# ChromDot_Ring_five_inch.net
KiCad netlist of a schematic drawn in EAGLE
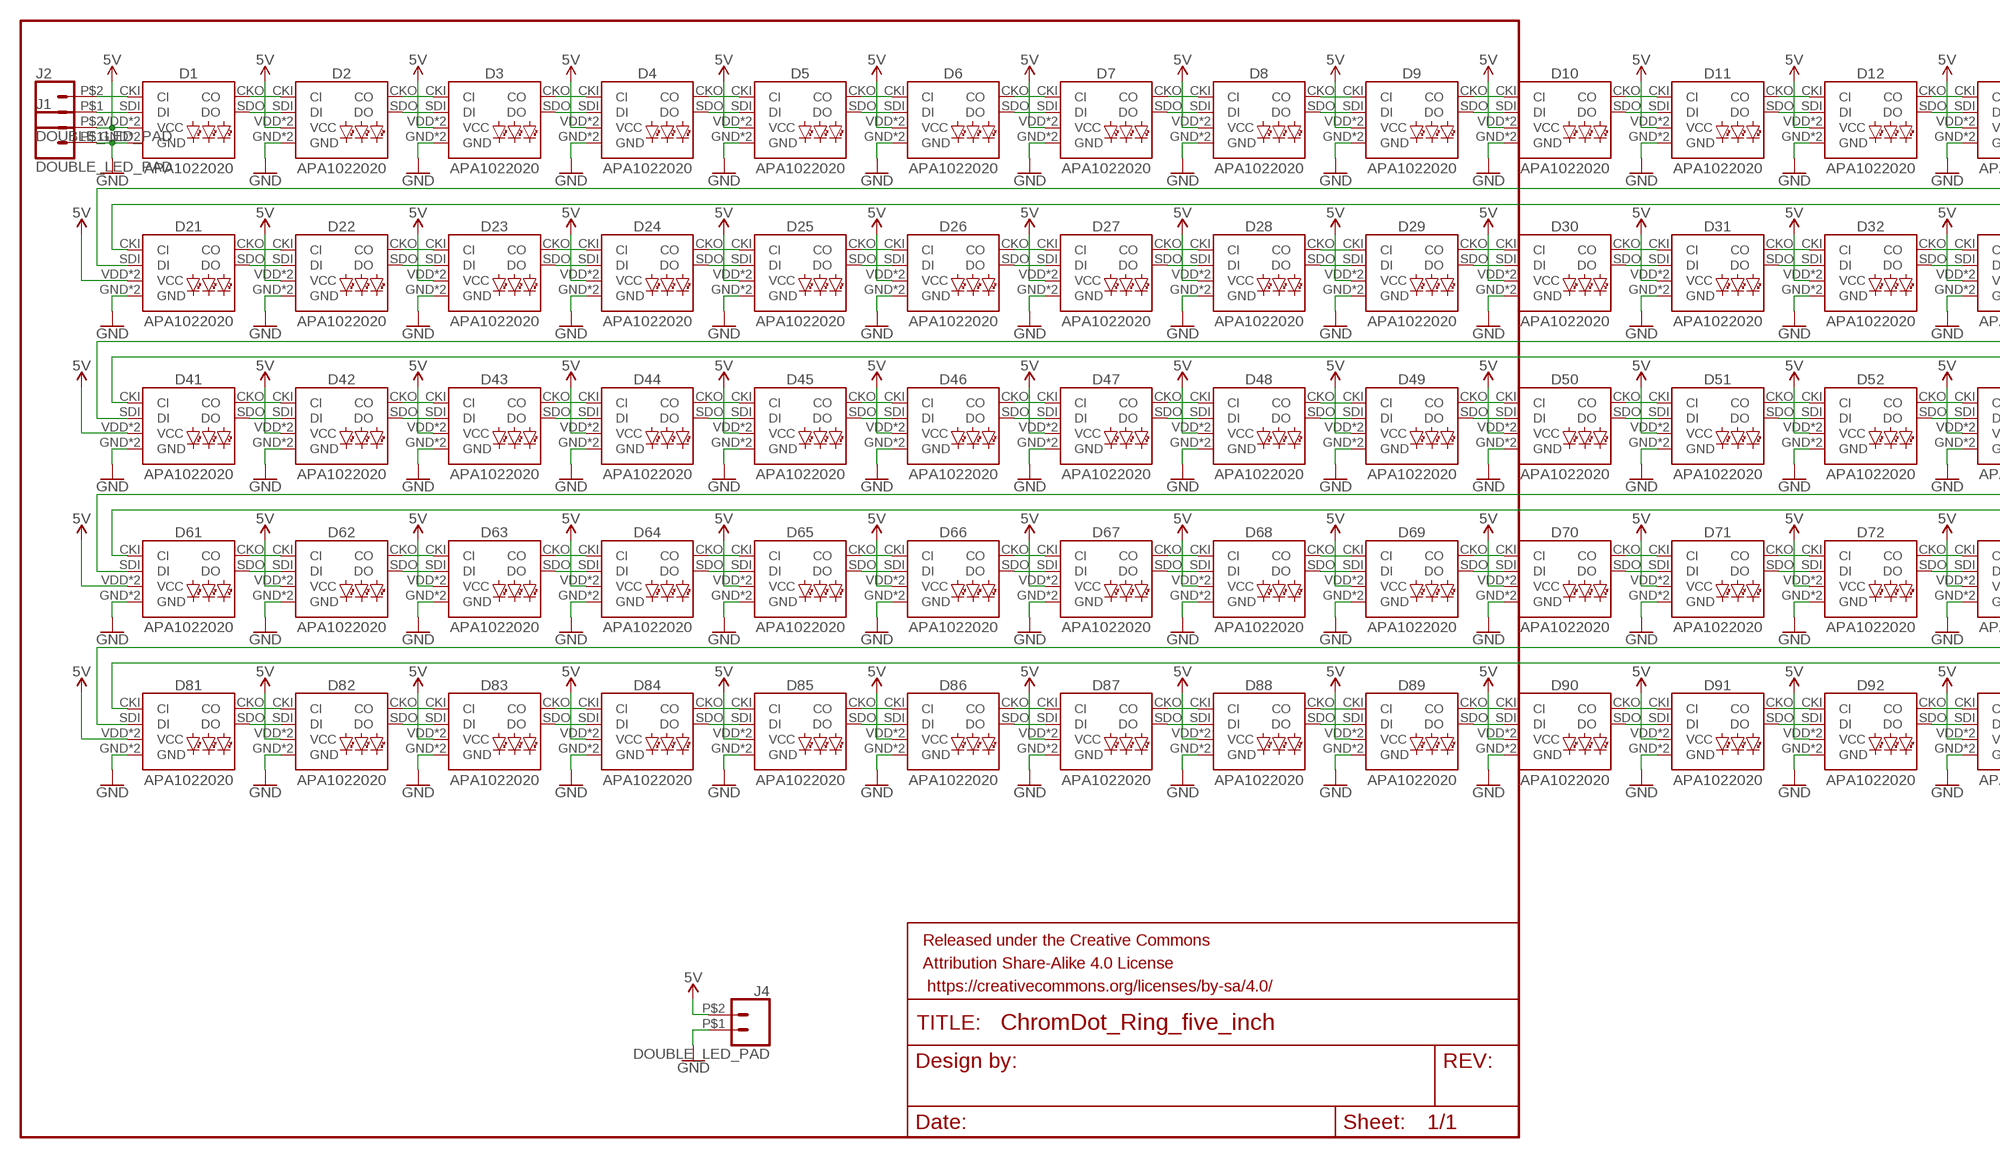
[diagram p0: schematic, sheet 1, part 1 of 2]
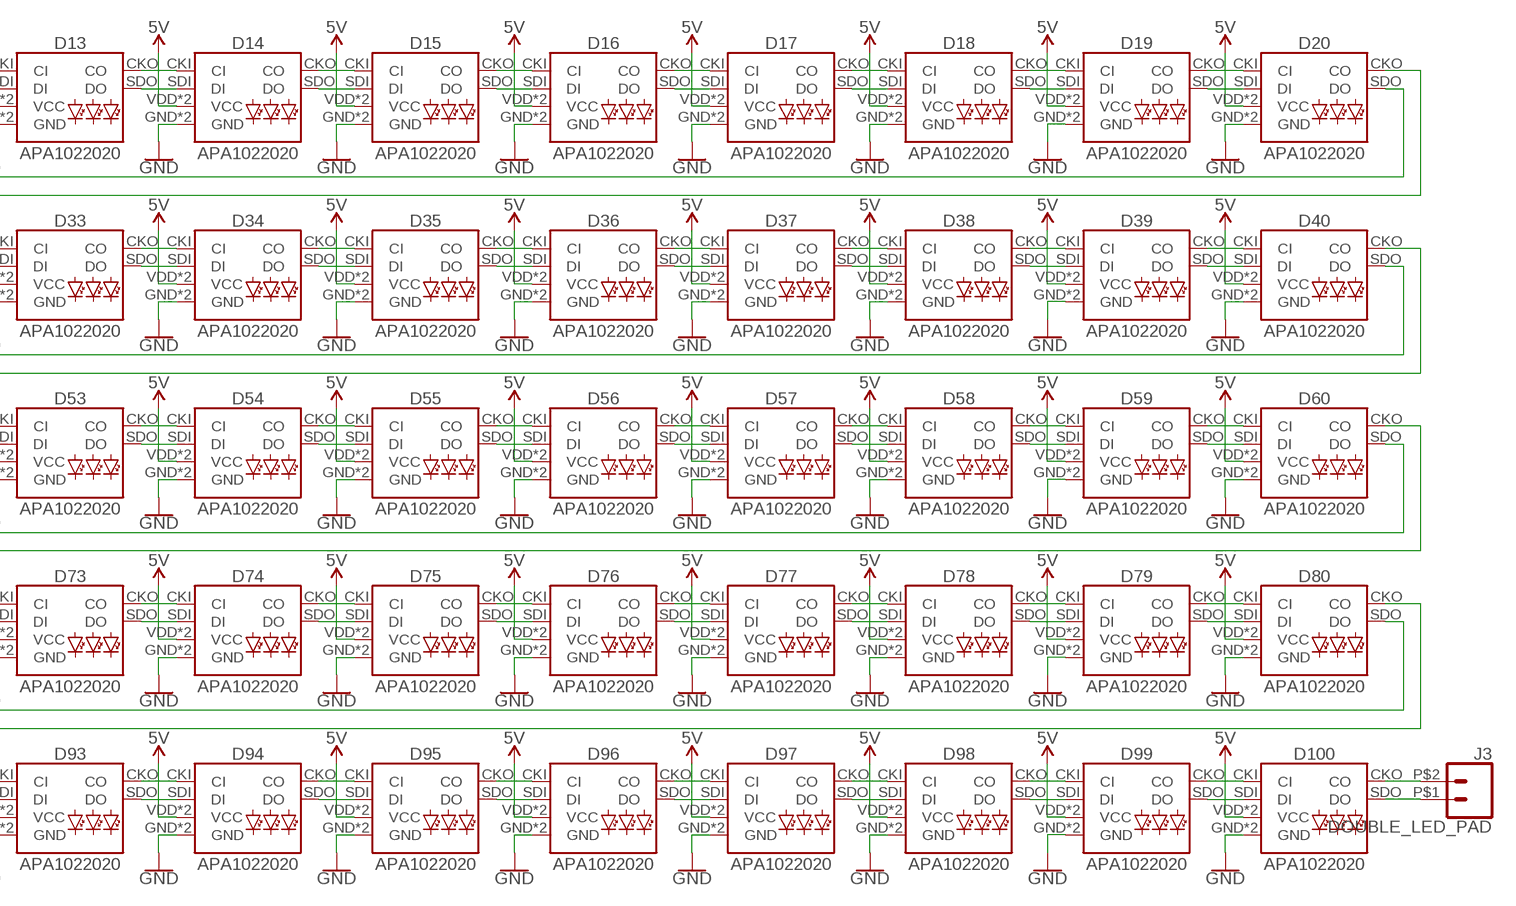
[diagram p1: schematic, sheet 1, part 2 of 2]

(export (version "E")
  (design (tool "Eeschema 10.0.6"))
  (components
    (comp (ref "D1")
      (value "APA1022020")
      (footprint "eagle-import:APA102-2020")
      (libsource (lib "eagle-import") (part "APA1022020"))
    )
    (comp (ref "D2")
      (value "APA1022020")
      (footprint "eagle-import:APA102-2020")
      (libsource (lib "eagle-import") (part "APA1022020"))
    )
    (comp (ref "D3")
      (value "APA1022020")
      (footprint "eagle-import:APA102-2020")
      (libsource (lib "eagle-import") (part "APA1022020"))
    )
    (comp (ref "D4")
      (value "APA1022020")
      (footprint "eagle-import:APA102-2020")
      (libsource (lib "eagle-import") (part "APA1022020"))
    )
    (comp (ref "D5")
      (value "APA1022020")
      (footprint "eagle-import:APA102-2020")
      (libsource (lib "eagle-import") (part "APA1022020"))
    )
    (comp (ref "D6")
      (value "APA1022020")
      (footprint "eagle-import:APA102-2020")
      (libsource (lib "eagle-import") (part "APA1022020"))
    )
    (comp (ref "D7")
      (value "APA1022020")
      (footprint "eagle-import:APA102-2020")
      (libsource (lib "eagle-import") (part "APA1022020"))
    )
    (comp (ref "D8")
      (value "APA1022020")
      (footprint "eagle-import:APA102-2020")
      (libsource (lib "eagle-import") (part "APA1022020"))
    )
    (comp (ref "D9")
      (value "APA1022020")
      (footprint "eagle-import:APA102-2020")
      (libsource (lib "eagle-import") (part "APA1022020"))
    )
    (comp (ref "D10")
      (value "APA1022020")
      (footprint "eagle-import:APA102-2020")
      (libsource (lib "eagle-import") (part "APA1022020"))
    )
    (comp (ref "D11")
      (value "APA1022020")
      (footprint "eagle-import:APA102-2020")
      (libsource (lib "eagle-import") (part "APA1022020"))
    )
    (comp (ref "D12")
      (value "APA1022020")
      (footprint "eagle-import:APA102-2020")
      (libsource (lib "eagle-import") (part "APA1022020"))
    )
    (comp (ref "D13")
      (value "APA1022020")
      (footprint "eagle-import:APA102-2020")
      (libsource (lib "eagle-import") (part "APA1022020"))
    )
    (comp (ref "D14")
      (value "APA1022020")
      (footprint "eagle-import:APA102-2020")
      (libsource (lib "eagle-import") (part "APA1022020"))
    )
    (comp (ref "D15")
      (value "APA1022020")
      (footprint "eagle-import:APA102-2020")
      (libsource (lib "eagle-import") (part "APA1022020"))
    )
    (comp (ref "D16")
      (value "APA1022020")
      (footprint "eagle-import:APA102-2020")
      (libsource (lib "eagle-import") (part "APA1022020"))
    )
    (comp (ref "D17")
      (value "APA1022020")
      (footprint "eagle-import:APA102-2020")
      (libsource (lib "eagle-import") (part "APA1022020"))
    )
    (comp (ref "D18")
      (value "APA1022020")
      (footprint "eagle-import:APA102-2020")
      (libsource (lib "eagle-import") (part "APA1022020"))
    )
    (comp (ref "D19")
      (value "APA1022020")
      (footprint "eagle-import:APA102-2020")
      (libsource (lib "eagle-import") (part "APA1022020"))
    )
    (comp (ref "D20")
      (value "APA1022020")
      (footprint "eagle-import:APA102-2020")
      (libsource (lib "eagle-import") (part "APA1022020"))
    )
    (comp (ref "D21")
      (value "APA1022020")
      (footprint "eagle-import:APA102-2020")
      (libsource (lib "eagle-import") (part "APA1022020"))
    )
    (comp (ref "D22")
      (value "APA1022020")
      (footprint "eagle-import:APA102-2020")
      (libsource (lib "eagle-import") (part "APA1022020"))
    )
    (comp (ref "D23")
      (value "APA1022020")
      (footprint "eagle-import:APA102-2020")
      (libsource (lib "eagle-import") (part "APA1022020"))
    )
    (comp (ref "D24")
      (value "APA1022020")
      (footprint "eagle-import:APA102-2020")
      (libsource (lib "eagle-import") (part "APA1022020"))
    )
    (comp (ref "D25")
      (value "APA1022020")
      (footprint "eagle-import:APA102-2020")
      (libsource (lib "eagle-import") (part "APA1022020"))
    )
    (comp (ref "D26")
      (value "APA1022020")
      (footprint "eagle-import:APA102-2020")
      (libsource (lib "eagle-import") (part "APA1022020"))
    )
    (comp (ref "D27")
      (value "APA1022020")
      (footprint "eagle-import:APA102-2020")
      (libsource (lib "eagle-import") (part "APA1022020"))
    )
    (comp (ref "D28")
      (value "APA1022020")
      (footprint "eagle-import:APA102-2020")
      (libsource (lib "eagle-import") (part "APA1022020"))
    )
    (comp (ref "D29")
      (value "APA1022020")
      (footprint "eagle-import:APA102-2020")
      (libsource (lib "eagle-import") (part "APA1022020"))
    )
    (comp (ref "D30")
      (value "APA1022020")
      (footprint "eagle-import:APA102-2020")
      (libsource (lib "eagle-import") (part "APA1022020"))
    )
    (comp (ref "D31")
      (value "APA1022020")
      (footprint "eagle-import:APA102-2020")
      (libsource (lib "eagle-import") (part "APA1022020"))
    )
    (comp (ref "D32")
      (value "APA1022020")
      (footprint "eagle-import:APA102-2020")
      (libsource (lib "eagle-import") (part "APA1022020"))
    )
    (comp (ref "D33")
      (value "APA1022020")
      (footprint "eagle-import:APA102-2020")
      (libsource (lib "eagle-import") (part "APA1022020"))
    )
    (comp (ref "D34")
      (value "APA1022020")
      (footprint "eagle-import:APA102-2020")
      (libsource (lib "eagle-import") (part "APA1022020"))
    )
    (comp (ref "D35")
      (value "APA1022020")
      (footprint "eagle-import:APA102-2020")
      (libsource (lib "eagle-import") (part "APA1022020"))
    )
    (comp (ref "D36")
      (value "APA1022020")
      (footprint "eagle-import:APA102-2020")
      (libsource (lib "eagle-import") (part "APA1022020"))
    )
    (comp (ref "D37")
      (value "APA1022020")
      (footprint "eagle-import:APA102-2020")
      (libsource (lib "eagle-import") (part "APA1022020"))
    )
    (comp (ref "D38")
      (value "APA1022020")
      (footprint "eagle-import:APA102-2020")
      (libsource (lib "eagle-import") (part "APA1022020"))
    )
    (comp (ref "D39")
      (value "APA1022020")
      (footprint "eagle-import:APA102-2020")
      (libsource (lib "eagle-import") (part "APA1022020"))
    )
    (comp (ref "D40")
      (value "APA1022020")
      (footprint "eagle-import:APA102-2020")
      (libsource (lib "eagle-import") (part "APA1022020"))
    )
    (comp (ref "D41")
      (value "APA1022020")
      (footprint "eagle-import:APA102-2020")
      (libsource (lib "eagle-import") (part "APA1022020"))
    )
    (comp (ref "D42")
      (value "APA1022020")
      (footprint "eagle-import:APA102-2020")
      (libsource (lib "eagle-import") (part "APA1022020"))
    )
    (comp (ref "D43")
      (value "APA1022020")
      (footprint "eagle-import:APA102-2020")
      (libsource (lib "eagle-import") (part "APA1022020"))
    )
    (comp (ref "D44")
      (value "APA1022020")
      (footprint "eagle-import:APA102-2020")
      (libsource (lib "eagle-import") (part "APA1022020"))
    )
    (comp (ref "D45")
      (value "APA1022020")
      (footprint "eagle-import:APA102-2020")
      (libsource (lib "eagle-import") (part "APA1022020"))
    )
    (comp (ref "D46")
      (value "APA1022020")
      (footprint "eagle-import:APA102-2020")
      (libsource (lib "eagle-import") (part "APA1022020"))
    )
    (comp (ref "D47")
      (value "APA1022020")
      (footprint "eagle-import:APA102-2020")
      (libsource (lib "eagle-import") (part "APA1022020"))
    )
    (comp (ref "D48")
      (value "APA1022020")
      (footprint "eagle-import:APA102-2020")
      (libsource (lib "eagle-import") (part "APA1022020"))
    )
    (comp (ref "D49")
      (value "APA1022020")
      (footprint "eagle-import:APA102-2020")
      (libsource (lib "eagle-import") (part "APA1022020"))
    )
    (comp (ref "D50")
      (value "APA1022020")
      (footprint "eagle-import:APA102-2020")
      (libsource (lib "eagle-import") (part "APA1022020"))
    )
    (comp (ref "D51")
      (value "APA1022020")
      (footprint "eagle-import:APA102-2020")
      (libsource (lib "eagle-import") (part "APA1022020"))
    )
    (comp (ref "D52")
      (value "APA1022020")
      (footprint "eagle-import:APA102-2020")
      (libsource (lib "eagle-import") (part "APA1022020"))
    )
    (comp (ref "D53")
      (value "APA1022020")
      (footprint "eagle-import:APA102-2020")
      (libsource (lib "eagle-import") (part "APA1022020"))
    )
    (comp (ref "D54")
      (value "APA1022020")
      (footprint "eagle-import:APA102-2020")
      (libsource (lib "eagle-import") (part "APA1022020"))
    )
    (comp (ref "D55")
      (value "APA1022020")
      (footprint "eagle-import:APA102-2020")
      (libsource (lib "eagle-import") (part "APA1022020"))
    )
    (comp (ref "D56")
      (value "APA1022020")
      (footprint "eagle-import:APA102-2020")
      (libsource (lib "eagle-import") (part "APA1022020"))
    )
    (comp (ref "D57")
      (value "APA1022020")
      (footprint "eagle-import:APA102-2020")
      (libsource (lib "eagle-import") (part "APA1022020"))
    )
    (comp (ref "D58")
      (value "APA1022020")
      (footprint "eagle-import:APA102-2020")
      (libsource (lib "eagle-import") (part "APA1022020"))
    )
    (comp (ref "D59")
      (value "APA1022020")
      (footprint "eagle-import:APA102-2020")
      (libsource (lib "eagle-import") (part "APA1022020"))
    )
    (comp (ref "D60")
      (value "APA1022020")
      (footprint "eagle-import:APA102-2020")
      (libsource (lib "eagle-import") (part "APA1022020"))
    )
    (comp (ref "D61")
      (value "APA1022020")
      (footprint "eagle-import:APA102-2020")
      (libsource (lib "eagle-import") (part "APA1022020"))
    )
    (comp (ref "D62")
      (value "APA1022020")
      (footprint "eagle-import:APA102-2020")
      (libsource (lib "eagle-import") (part "APA1022020"))
    )
    (comp (ref "D63")
      (value "APA1022020")
      (footprint "eagle-import:APA102-2020")
      (libsource (lib "eagle-import") (part "APA1022020"))
    )
    (comp (ref "D64")
      (value "APA1022020")
      (footprint "eagle-import:APA102-2020")
      (libsource (lib "eagle-import") (part "APA1022020"))
    )
    (comp (ref "D65")
      (value "APA1022020")
      (footprint "eagle-import:APA102-2020")
      (libsource (lib "eagle-import") (part "APA1022020"))
    )
    (comp (ref "D66")
      (value "APA1022020")
      (footprint "eagle-import:APA102-2020")
      (libsource (lib "eagle-import") (part "APA1022020"))
    )
    (comp (ref "D67")
      (value "APA1022020")
      (footprint "eagle-import:APA102-2020")
      (libsource (lib "eagle-import") (part "APA1022020"))
    )
    (comp (ref "D68")
      (value "APA1022020")
      (footprint "eagle-import:APA102-2020")
      (libsource (lib "eagle-import") (part "APA1022020"))
    )
    (comp (ref "D69")
      (value "APA1022020")
      (footprint "eagle-import:APA102-2020")
      (libsource (lib "eagle-import") (part "APA1022020"))
    )
    (comp (ref "D70")
      (value "APA1022020")
      (footprint "eagle-import:APA102-2020")
      (libsource (lib "eagle-import") (part "APA1022020"))
    )
    (comp (ref "D71")
      (value "APA1022020")
      (footprint "eagle-import:APA102-2020")
      (libsource (lib "eagle-import") (part "APA1022020"))
    )
    (comp (ref "D72")
      (value "APA1022020")
      (footprint "eagle-import:APA102-2020")
      (libsource (lib "eagle-import") (part "APA1022020"))
    )
    (comp (ref "D73")
      (value "APA1022020")
      (footprint "eagle-import:APA102-2020")
      (libsource (lib "eagle-import") (part "APA1022020"))
    )
    (comp (ref "D74")
      (value "APA1022020")
      (footprint "eagle-import:APA102-2020")
      (libsource (lib "eagle-import") (part "APA1022020"))
    )
    (comp (ref "D75")
      (value "APA1022020")
      (footprint "eagle-import:APA102-2020")
      (libsource (lib "eagle-import") (part "APA1022020"))
    )
    (comp (ref "D76")
      (value "APA1022020")
      (footprint "eagle-import:APA102-2020")
      (libsource (lib "eagle-import") (part "APA1022020"))
    )
    (comp (ref "D77")
      (value "APA1022020")
      (footprint "eagle-import:APA102-2020")
      (libsource (lib "eagle-import") (part "APA1022020"))
    )
    (comp (ref "D78")
      (value "APA1022020")
      (footprint "eagle-import:APA102-2020")
      (libsource (lib "eagle-import") (part "APA1022020"))
    )
    (comp (ref "D79")
      (value "APA1022020")
      (footprint "eagle-import:APA102-2020")
      (libsource (lib "eagle-import") (part "APA1022020"))
    )
    (comp (ref "D80")
      (value "APA1022020")
      (footprint "eagle-import:APA102-2020")
      (libsource (lib "eagle-import") (part "APA1022020"))
    )
    (comp (ref "D81")
      (value "APA1022020")
      (footprint "eagle-import:APA102-2020")
      (libsource (lib "eagle-import") (part "APA1022020"))
    )
    (comp (ref "D82")
      (value "APA1022020")
      (footprint "eagle-import:APA102-2020")
      (libsource (lib "eagle-import") (part "APA1022020"))
    )
    (comp (ref "D83")
      (value "APA1022020")
      (footprint "eagle-import:APA102-2020")
      (libsource (lib "eagle-import") (part "APA1022020"))
    )
    (comp (ref "D84")
      (value "APA1022020")
      (footprint "eagle-import:APA102-2020")
      (libsource (lib "eagle-import") (part "APA1022020"))
    )
    (comp (ref "D85")
      (value "APA1022020")
      (footprint "eagle-import:APA102-2020")
      (libsource (lib "eagle-import") (part "APA1022020"))
    )
    (comp (ref "D86")
      (value "APA1022020")
      (footprint "eagle-import:APA102-2020")
      (libsource (lib "eagle-import") (part "APA1022020"))
    )
    (comp (ref "D87")
      (value "APA1022020")
      (footprint "eagle-import:APA102-2020")
      (libsource (lib "eagle-import") (part "APA1022020"))
    )
    (comp (ref "D88")
      (value "APA1022020")
      (footprint "eagle-import:APA102-2020")
      (libsource (lib "eagle-import") (part "APA1022020"))
    )
    (comp (ref "D89")
      (value "APA1022020")
      (footprint "eagle-import:APA102-2020")
      (libsource (lib "eagle-import") (part "APA1022020"))
    )
    (comp (ref "D90")
      (value "APA1022020")
      (footprint "eagle-import:APA102-2020")
      (libsource (lib "eagle-import") (part "APA1022020"))
    )
    (comp (ref "D91")
      (value "APA1022020")
      (footprint "eagle-import:APA102-2020")
      (libsource (lib "eagle-import") (part "APA1022020"))
    )
    (comp (ref "D92")
      (value "APA1022020")
      (footprint "eagle-import:APA102-2020")
      (libsource (lib "eagle-import") (part "APA1022020"))
    )
    (comp (ref "D93")
      (value "APA1022020")
      (footprint "eagle-import:APA102-2020")
      (libsource (lib "eagle-import") (part "APA1022020"))
    )
    (comp (ref "D94")
      (value "APA1022020")
      (footprint "eagle-import:APA102-2020")
      (libsource (lib "eagle-import") (part "APA1022020"))
    )
    (comp (ref "D95")
      (value "APA1022020")
      (footprint "eagle-import:APA102-2020")
      (libsource (lib "eagle-import") (part "APA1022020"))
    )
    (comp (ref "D96")
      (value "APA1022020")
      (footprint "eagle-import:APA102-2020")
      (libsource (lib "eagle-import") (part "APA1022020"))
    )
    (comp (ref "D97")
      (value "APA1022020")
      (footprint "eagle-import:APA102-2020")
      (libsource (lib "eagle-import") (part "APA1022020"))
    )
    (comp (ref "D98")
      (value "APA1022020")
      (footprint "eagle-import:APA102-2020")
      (libsource (lib "eagle-import") (part "APA1022020"))
    )
    (comp (ref "D99")
      (value "APA1022020")
      (footprint "eagle-import:APA102-2020")
      (libsource (lib "eagle-import") (part "APA1022020"))
    )
    (comp (ref "D100")
      (value "APA1022020")
      (footprint "eagle-import:APA102-2020")
      (libsource (lib "eagle-import") (part "APA1022020"))
    )
    (comp (ref "FRAME1")
      (value "FRAME-LETTER")
      (footprint "eagle-import:CREATIVE_COMMONS")
      (libsource (lib "eagle-import") (part "FRAME-LETTER"))
    )
    (comp (ref "J1")
      (value "DOUBLE_LED_PAD")
      (footprint "eagle-import:DOUBLELEDPAD")
      (libsource (lib "eagle-import") (part "DOUBLE_LED_PAD"))
    )
    (comp (ref "J2")
      (value "DOUBLE_LED_PAD")
      (footprint "eagle-import:DOUBLELEDPAD")
      (libsource (lib "eagle-import") (part "DOUBLE_LED_PAD"))
    )
    (comp (ref "J3")
      (value "DOUBLE_LED_PAD")
      (footprint "eagle-import:DOUBLELEDPAD")
      (libsource (lib "eagle-import") (part "DOUBLE_LED_PAD"))
    )
    (comp (ref "J4")
      (value "DOUBLE_LED_PAD")
      (footprint "eagle-import:DOUBLELEDPAD")
      (libsource (lib "eagle-import") (part "DOUBLE_LED_PAD"))
    )
  )
  (nets
    (net (code "1") (name "5V") (class "Default")
      (node (ref "D1") (pin "VDD") (pinfunction "VCC_VDD") (pintype "bidirectional"))
      (node (ref "D1") (pin "VDDPAD") (pinfunction "VCC_VDDPAD") (pintype "bidirectional"))
      (node (ref "D10") (pin "VDD") (pinfunction "VCC_VDD") (pintype "bidirectional"))
      (node (ref "D10") (pin "VDDPAD") (pinfunction "VCC_VDDPAD") (pintype "bidirectional"))
      (node (ref "D100") (pin "VDD") (pinfunction "VCC_VDD") (pintype "bidirectional"))
      (node (ref "D100") (pin "VDDPAD") (pinfunction "VCC_VDDPAD") (pintype "bidirectional"))
      (node (ref "D11") (pin "VDD") (pinfunction "VCC_VDD") (pintype "bidirectional"))
      (node (ref "D11") (pin "VDDPAD") (pinfunction "VCC_VDDPAD") (pintype "bidirectional"))
      (node (ref "D12") (pin "VDD") (pinfunction "VCC_VDD") (pintype "bidirectional"))
      (node (ref "D12") (pin "VDDPAD") (pinfunction "VCC_VDDPAD") (pintype "bidirectional"))
      (node (ref "D13") (pin "VDD") (pinfunction "VCC_VDD") (pintype "bidirectional"))
      (node (ref "D13") (pin "VDDPAD") (pinfunction "VCC_VDDPAD") (pintype "bidirectional"))
      (node (ref "D14") (pin "VDD") (pinfunction "VCC_VDD") (pintype "bidirectional"))
      (node (ref "D14") (pin "VDDPAD") (pinfunction "VCC_VDDPAD") (pintype "bidirectional"))
      (node (ref "D15") (pin "VDD") (pinfunction "VCC_VDD") (pintype "bidirectional"))
      (node (ref "D15") (pin "VDDPAD") (pinfunction "VCC_VDDPAD") (pintype "bidirectional"))
      (node (ref "D16") (pin "VDD") (pinfunction "VCC_VDD") (pintype "bidirectional"))
      (node (ref "D16") (pin "VDDPAD") (pinfunction "VCC_VDDPAD") (pintype "bidirectional"))
      (node (ref "D17") (pin "VDD") (pinfunction "VCC_VDD") (pintype "bidirectional"))
      (node (ref "D17") (pin "VDDPAD") (pinfunction "VCC_VDDPAD") (pintype "bidirectional"))
      (node (ref "D18") (pin "VDD") (pinfunction "VCC_VDD") (pintype "bidirectional"))
      (node (ref "D18") (pin "VDDPAD") (pinfunction "VCC_VDDPAD") (pintype "bidirectional"))
      (node (ref "D19") (pin "VDD") (pinfunction "VCC_VDD") (pintype "bidirectional"))
      (node (ref "D19") (pin "VDDPAD") (pinfunction "VCC_VDDPAD") (pintype "bidirectional"))
      (node (ref "D2") (pin "VDD") (pinfunction "VCC_VDD") (pintype "bidirectional"))
      (node (ref "D2") (pin "VDDPAD") (pinfunction "VCC_VDDPAD") (pintype "bidirectional"))
      (node (ref "D20") (pin "VDD") (pinfunction "VCC_VDD") (pintype "bidirectional"))
      (node (ref "D20") (pin "VDDPAD") (pinfunction "VCC_VDDPAD") (pintype "bidirectional"))
      (node (ref "D21") (pin "VDD") (pinfunction "VCC_VDD") (pintype "bidirectional"))
      (node (ref "D21") (pin "VDDPAD") (pinfunction "VCC_VDDPAD") (pintype "bidirectional"))
      (node (ref "D22") (pin "VDD") (pinfunction "VCC_VDD") (pintype "bidirectional"))
      (node (ref "D22") (pin "VDDPAD") (pinfunction "VCC_VDDPAD") (pintype "bidirectional"))
      (node (ref "D23") (pin "VDD") (pinfunction "VCC_VDD") (pintype "bidirectional"))
      (node (ref "D23") (pin "VDDPAD") (pinfunction "VCC_VDDPAD") (pintype "bidirectional"))
      (node (ref "D24") (pin "VDD") (pinfunction "VCC_VDD") (pintype "bidirectional"))
      (node (ref "D24") (pin "VDDPAD") (pinfunction "VCC_VDDPAD") (pintype "bidirectional"))
      (node (ref "D25") (pin "VDD") (pinfunction "VCC_VDD") (pintype "bidirectional"))
      (node (ref "D25") (pin "VDDPAD") (pinfunction "VCC_VDDPAD") (pintype "bidirectional"))
      (node (ref "D26") (pin "VDD") (pinfunction "VCC_VDD") (pintype "bidirectional"))
      (node (ref "D26") (pin "VDDPAD") (pinfunction "VCC_VDDPAD") (pintype "bidirectional"))
      (node (ref "D27") (pin "VDD") (pinfunction "VCC_VDD") (pintype "bidirectional"))
      (node (ref "D27") (pin "VDDPAD") (pinfunction "VCC_VDDPAD") (pintype "bidirectional"))
      (node (ref "D28") (pin "VDD") (pinfunction "VCC_VDD") (pintype "bidirectional"))
      (node (ref "D28") (pin "VDDPAD") (pinfunction "VCC_VDDPAD") (pintype "bidirectional"))
      (node (ref "D29") (pin "VDD") (pinfunction "VCC_VDD") (pintype "bidirectional"))
      (node (ref "D29") (pin "VDDPAD") (pinfunction "VCC_VDDPAD") (pintype "bidirectional"))
      (node (ref "D3") (pin "VDD") (pinfunction "VCC_VDD") (pintype "bidirectional"))
      (node (ref "D3") (pin "VDDPAD") (pinfunction "VCC_VDDPAD") (pintype "bidirectional"))
      (node (ref "D30") (pin "VDD") (pinfunction "VCC_VDD") (pintype "bidirectional"))
      (node (ref "D30") (pin "VDDPAD") (pinfunction "VCC_VDDPAD") (pintype "bidirectional"))
      (node (ref "D31") (pin "VDD") (pinfunction "VCC_VDD") (pintype "bidirectional"))
      (node (ref "D31") (pin "VDDPAD") (pinfunction "VCC_VDDPAD") (pintype "bidirectional"))
      (node (ref "D32") (pin "VDD") (pinfunction "VCC_VDD") (pintype "bidirectional"))
      (node (ref "D32") (pin "VDDPAD") (pinfunction "VCC_VDDPAD") (pintype "bidirectional"))
      (node (ref "D33") (pin "VDD") (pinfunction "VCC_VDD") (pintype "bidirectional"))
      (node (ref "D33") (pin "VDDPAD") (pinfunction "VCC_VDDPAD") (pintype "bidirectional"))
      (node (ref "D34") (pin "VDD") (pinfunction "VCC_VDD") (pintype "bidirectional"))
      (node (ref "D34") (pin "VDDPAD") (pinfunction "VCC_VDDPAD") (pintype "bidirectional"))
      (node (ref "D35") (pin "VDD") (pinfunction "VCC_VDD") (pintype "bidirectional"))
      (node (ref "D35") (pin "VDDPAD") (pinfunction "VCC_VDDPAD") (pintype "bidirectional"))
      (node (ref "D36") (pin "VDD") (pinfunction "VCC_VDD") (pintype "bidirectional"))
      (node (ref "D36") (pin "VDDPAD") (pinfunction "VCC_VDDPAD") (pintype "bidirectional"))
      (node (ref "D37") (pin "VDD") (pinfunction "VCC_VDD") (pintype "bidirectional"))
      (node (ref "D37") (pin "VDDPAD") (pinfunction "VCC_VDDPAD") (pintype "bidirectional"))
      (node (ref "D38") (pin "VDD") (pinfunction "VCC_VDD") (pintype "bidirectional"))
      (node (ref "D38") (pin "VDDPAD") (pinfunction "VCC_VDDPAD") (pintype "bidirectional"))
      (node (ref "D39") (pin "VDD") (pinfunction "VCC_VDD") (pintype "bidirectional"))
      (node (ref "D39") (pin "VDDPAD") (pinfunction "VCC_VDDPAD") (pintype "bidirectional"))
      (node (ref "D4") (pin "VDD") (pinfunction "VCC_VDD") (pintype "bidirectional"))
      (node (ref "D4") (pin "VDDPAD") (pinfunction "VCC_VDDPAD") (pintype "bidirectional"))
      (node (ref "D40") (pin "VDD") (pinfunction "VCC_VDD") (pintype "bidirectional"))
      (node (ref "D40") (pin "VDDPAD") (pinfunction "VCC_VDDPAD") (pintype "bidirectional"))
      (node (ref "D41") (pin "VDD") (pinfunction "VCC_VDD") (pintype "bidirectional"))
      (node (ref "D41") (pin "VDDPAD") (pinfunction "VCC_VDDPAD") (pintype "bidirectional"))
      (node (ref "D42") (pin "VDD") (pinfunction "VCC_VDD") (pintype "bidirectional"))
      (node (ref "D42") (pin "VDDPAD") (pinfunction "VCC_VDDPAD") (pintype "bidirectional"))
      (node (ref "D43") (pin "VDD") (pinfunction "VCC_VDD") (pintype "bidirectional"))
      (node (ref "D43") (pin "VDDPAD") (pinfunction "VCC_VDDPAD") (pintype "bidirectional"))
      (node (ref "D44") (pin "VDD") (pinfunction "VCC_VDD") (pintype "bidirectional"))
      (node (ref "D44") (pin "VDDPAD") (pinfunction "VCC_VDDPAD") (pintype "bidirectional"))
      (node (ref "D45") (pin "VDD") (pinfunction "VCC_VDD") (pintype "bidirectional"))
      (node (ref "D45") (pin "VDDPAD") (pinfunction "VCC_VDDPAD") (pintype "bidirectional"))
      (node (ref "D46") (pin "VDD") (pinfunction "VCC_VDD") (pintype "bidirectional"))
      (node (ref "D46") (pin "VDDPAD") (pinfunction "VCC_VDDPAD") (pintype "bidirectional"))
      (node (ref "D47") (pin "VDD") (pinfunction "VCC_VDD") (pintype "bidirectional"))
      (node (ref "D47") (pin "VDDPAD") (pinfunction "VCC_VDDPAD") (pintype "bidirectional"))
      (node (ref "D48") (pin "VDD") (pinfunction "VCC_VDD") (pintype "bidirectional"))
      (node (ref "D48") (pin "VDDPAD") (pinfunction "VCC_VDDPAD") (pintype "bidirectional"))
      (node (ref "D49") (pin "VDD") (pinfunction "VCC_VDD") (pintype "bidirectional"))
      (node (ref "D49") (pin "VDDPAD") (pinfunction "VCC_VDDPAD") (pintype "bidirectional"))
      (node (ref "D5") (pin "VDD") (pinfunction "VCC_VDD") (pintype "bidirectional"))
      (node (ref "D5") (pin "VDDPAD") (pinfunction "VCC_VDDPAD") (pintype "bidirectional"))
      (node (ref "D50") (pin "VDD") (pinfunction "VCC_VDD") (pintype "bidirectional"))
      (node (ref "D50") (pin "VDDPAD") (pinfunction "VCC_VDDPAD") (pintype "bidirectional"))
      (node (ref "D51") (pin "VDD") (pinfunction "VCC_VDD") (pintype "bidirectional"))
      (node (ref "D51") (pin "VDDPAD") (pinfunction "VCC_VDDPAD") (pintype "bidirectional"))
      (node (ref "D52") (pin "VDD") (pinfunction "VCC_VDD") (pintype "bidirectional"))
      (node (ref "D52") (pin "VDDPAD") (pinfunction "VCC_VDDPAD") (pintype "bidirectional"))
      (node (ref "D53") (pin "VDD") (pinfunction "VCC_VDD") (pintype "bidirectional"))
      (node (ref "D53") (pin "VDDPAD") (pinfunction "VCC_VDDPAD") (pintype "bidirectional"))
      (node (ref "D54") (pin "VDD") (pinfunction "VCC_VDD") (pintype "bidirectional"))
      (node (ref "D54") (pin "VDDPAD") (pinfunction "VCC_VDDPAD") (pintype "bidirectional"))
      (node (ref "D55") (pin "VDD") (pinfunction "VCC_VDD") (pintype "bidirectional"))
      (node (ref "D55") (pin "VDDPAD") (pinfunction "VCC_VDDPAD") (pintype "bidirectional"))
      (node (ref "D56") (pin "VDD") (pinfunction "VCC_VDD") (pintype "bidirectional"))
      (node (ref "D56") (pin "VDDPAD") (pinfunction "VCC_VDDPAD") (pintype "bidirectional"))
      (node (ref "D57") (pin "VDD") (pinfunction "VCC_VDD") (pintype "bidirectional"))
      (node (ref "D57") (pin "VDDPAD") (pinfunction "VCC_VDDPAD") (pintype "bidirectional"))
      (node (ref "D58") (pin "VDD") (pinfunction "VCC_VDD") (pintype "bidirectional"))
      (node (ref "D58") (pin "VDDPAD") (pinfunction "VCC_VDDPAD") (pintype "bidirectional"))
      (node (ref "D59") (pin "VDD") (pinfunction "VCC_VDD") (pintype "bidirectional"))
      (node (ref "D59") (pin "VDDPAD") (pinfunction "VCC_VDDPAD") (pintype "bidirectional"))
      (node (ref "D6") (pin "VDD") (pinfunction "VCC_VDD") (pintype "bidirectional"))
      (node (ref "D6") (pin "VDDPAD") (pinfunction "VCC_VDDPAD") (pintype "bidirectional"))
      (node (ref "D60") (pin "VDD") (pinfunction "VCC_VDD") (pintype "bidirectional"))
      (node (ref "D60") (pin "VDDPAD") (pinfunction "VCC_VDDPAD") (pintype "bidirectional"))
      (node (ref "D61") (pin "VDD") (pinfunction "VCC_VDD") (pintype "bidirectional"))
      (node (ref "D61") (pin "VDDPAD") (pinfunction "VCC_VDDPAD") (pintype "bidirectional"))
      (node (ref "D62") (pin "VDD") (pinfunction "VCC_VDD") (pintype "bidirectional"))
      (node (ref "D62") (pin "VDDPAD") (pinfunction "VCC_VDDPAD") (pintype "bidirectional"))
      (node (ref "D63") (pin "VDD") (pinfunction "VCC_VDD") (pintype "bidirectional"))
      (node (ref "D63") (pin "VDDPAD") (pinfunction "VCC_VDDPAD") (pintype "bidirectional"))
      (node (ref "D64") (pin "VDD") (pinfunction "VCC_VDD") (pintype "bidirectional"))
      (node (ref "D64") (pin "VDDPAD") (pinfunction "VCC_VDDPAD") (pintype "bidirectional"))
      (node (ref "D65") (pin "VDD") (pinfunction "VCC_VDD") (pintype "bidirectional"))
      (node (ref "D65") (pin "VDDPAD") (pinfunction "VCC_VDDPAD") (pintype "bidirectional"))
      (node (ref "D66") (pin "VDD") (pinfunction "VCC_VDD") (pintype "bidirectional"))
      (node (ref "D66") (pin "VDDPAD") (pinfunction "VCC_VDDPAD") (pintype "bidirectional"))
      (node (ref "D67") (pin "VDD") (pinfunction "VCC_VDD") (pintype "bidirectional"))
      (node (ref "D67") (pin "VDDPAD") (pinfunction "VCC_VDDPAD") (pintype "bidirectional"))
      (node (ref "D68") (pin "VDD") (pinfunction "VCC_VDD") (pintype "bidirectional"))
      (node (ref "D68") (pin "VDDPAD") (pinfunction "VCC_VDDPAD") (pintype "bidirectional"))
      (node (ref "D69") (pin "VDD") (pinfunction "VCC_VDD") (pintype "bidirectional"))
      (node (ref "D69") (pin "VDDPAD") (pinfunction "VCC_VDDPAD") (pintype "bidirectional"))
      (node (ref "D7") (pin "VDD") (pinfunction "VCC_VDD") (pintype "bidirectional"))
      (node (ref "D7") (pin "VDDPAD") (pinfunction "VCC_VDDPAD") (pintype "bidirectional"))
      (node (ref "D70") (pin "VDD") (pinfunction "VCC_VDD") (pintype "bidirectional"))
      (node (ref "D70") (pin "VDDPAD") (pinfunction "VCC_VDDPAD") (pintype "bidirectional"))
      (node (ref "D71") (pin "VDD") (pinfunction "VCC_VDD") (pintype "bidirectional"))
      (node (ref "D71") (pin "VDDPAD") (pinfunction "VCC_VDDPAD") (pintype "bidirectional"))
      (node (ref "D72") (pin "VDD") (pinfunction "VCC_VDD") (pintype "bidirectional"))
      (node (ref "D72") (pin "VDDPAD") (pinfunction "VCC_VDDPAD") (pintype "bidirectional"))
      (node (ref "D73") (pin "VDD") (pinfunction "VCC_VDD") (pintype "bidirectional"))
      (node (ref "D73") (pin "VDDPAD") (pinfunction "VCC_VDDPAD") (pintype "bidirectional"))
      (node (ref "D74") (pin "VDD") (pinfunction "VCC_VDD") (pintype "bidirectional"))
      (node (ref "D74") (pin "VDDPAD") (pinfunction "VCC_VDDPAD") (pintype "bidirectional"))
      (node (ref "D75") (pin "VDD") (pinfunction "VCC_VDD") (pintype "bidirectional"))
      (node (ref "D75") (pin "VDDPAD") (pinfunction "VCC_VDDPAD") (pintype "bidirectional"))
      (node (ref "D76") (pin "VDD") (pinfunction "VCC_VDD") (pintype "bidirectional"))
      (node (ref "D76") (pin "VDDPAD") (pinfunction "VCC_VDDPAD") (pintype "bidirectional"))
      (node (ref "D77") (pin "VDD") (pinfunction "VCC_VDD") (pintype "bidirectional"))
      (node (ref "D77") (pin "VDDPAD") (pinfunction "VCC_VDDPAD") (pintype "bidirectional"))
      (node (ref "D78") (pin "VDD") (pinfunction "VCC_VDD") (pintype "bidirectional"))
      (node (ref "D78") (pin "VDDPAD") (pinfunction "VCC_VDDPAD") (pintype "bidirectional"))
      (node (ref "D79") (pin "VDD") (pinfunction "VCC_VDD") (pintype "bidirectional"))
      (node (ref "D79") (pin "VDDPAD") (pinfunction "VCC_VDDPAD") (pintype "bidirectional"))
      (node (ref "D8") (pin "VDD") (pinfunction "VCC_VDD") (pintype "bidirectional"))
      (node (ref "D8") (pin "VDDPAD") (pinfunction "VCC_VDDPAD") (pintype "bidirectional"))
      (node (ref "D80") (pin "VDD") (pinfunction "VCC_VDD") (pintype "bidirectional"))
      (node (ref "D80") (pin "VDDPAD") (pinfunction "VCC_VDDPAD") (pintype "bidirectional"))
      (node (ref "D81") (pin "VDD") (pinfunction "VCC_VDD") (pintype "bidirectional"))
      (node (ref "D81") (pin "VDDPAD") (pinfunction "VCC_VDDPAD") (pintype "bidirectional"))
      (node (ref "D82") (pin "VDD") (pinfunction "VCC_VDD") (pintype "bidirectional"))
      (node (ref "D82") (pin "VDDPAD") (pinfunction "VCC_VDDPAD") (pintype "bidirectional"))
      (node (ref "D83") (pin "VDD") (pinfunction "VCC_VDD") (pintype "bidirectional"))
      (node (ref "D83") (pin "VDDPAD") (pinfunction "VCC_VDDPAD") (pintype "bidirectional"))
      (node (ref "D84") (pin "VDD") (pinfunction "VCC_VDD") (pintype "bidirectional"))
      (node (ref "D84") (pin "VDDPAD") (pinfunction "VCC_VDDPAD") (pintype "bidirectional"))
      (node (ref "D85") (pin "VDD") (pinfunction "VCC_VDD") (pintype "bidirectional"))
      (node (ref "D85") (pin "VDDPAD") (pinfunction "VCC_VDDPAD") (pintype "bidirectional"))
      (node (ref "D86") (pin "VDD") (pinfunction "VCC_VDD") (pintype "bidirectional"))
      (node (ref "D86") (pin "VDDPAD") (pinfunction "VCC_VDDPAD") (pintype "bidirectional"))
      (node (ref "D87") (pin "VDD") (pinfunction "VCC_VDD") (pintype "bidirectional"))
      (node (ref "D87") (pin "VDDPAD") (pinfunction "VCC_VDDPAD") (pintype "bidirectional"))
      (node (ref "D88") (pin "VDD") (pinfunction "VCC_VDD") (pintype "bidirectional"))
      (node (ref "D88") (pin "VDDPAD") (pinfunction "VCC_VDDPAD") (pintype "bidirectional"))
      (node (ref "D89") (pin "VDD") (pinfunction "VCC_VDD") (pintype "bidirectional"))
      (node (ref "D89") (pin "VDDPAD") (pinfunction "VCC_VDDPAD") (pintype "bidirectional"))
      (node (ref "D9") (pin "VDD") (pinfunction "VCC_VDD") (pintype "bidirectional"))
      (node (ref "D9") (pin "VDDPAD") (pinfunction "VCC_VDDPAD") (pintype "bidirectional"))
      (node (ref "D90") (pin "VDD") (pinfunction "VCC_VDD") (pintype "bidirectional"))
      (node (ref "D90") (pin "VDDPAD") (pinfunction "VCC_VDDPAD") (pintype "bidirectional"))
      (node (ref "D91") (pin "VDD") (pinfunction "VCC_VDD") (pintype "bidirectional"))
      (node (ref "D91") (pin "VDDPAD") (pinfunction "VCC_VDDPAD") (pintype "bidirectional"))
      (node (ref "D92") (pin "VDD") (pinfunction "VCC_VDD") (pintype "bidirectional"))
      (node (ref "D92") (pin "VDDPAD") (pinfunction "VCC_VDDPAD") (pintype "bidirectional"))
      (node (ref "D93") (pin "VDD") (pinfunction "VCC_VDD") (pintype "bidirectional"))
      (node (ref "D93") (pin "VDDPAD") (pinfunction "VCC_VDDPAD") (pintype "bidirectional"))
      (node (ref "D94") (pin "VDD") (pinfunction "VCC_VDD") (pintype "bidirectional"))
      (node (ref "D94") (pin "VDDPAD") (pinfunction "VCC_VDDPAD") (pintype "bidirectional"))
      (node (ref "D95") (pin "VDD") (pinfunction "VCC_VDD") (pintype "bidirectional"))
      (node (ref "D95") (pin "VDDPAD") (pinfunction "VCC_VDDPAD") (pintype "bidirectional"))
      (node (ref "D96") (pin "VDD") (pinfunction "VCC_VDD") (pintype "bidirectional"))
      (node (ref "D96") (pin "VDDPAD") (pinfunction "VCC_VDDPAD") (pintype "bidirectional"))
      (node (ref "D97") (pin "VDD") (pinfunction "VCC_VDD") (pintype "bidirectional"))
      (node (ref "D97") (pin "VDDPAD") (pinfunction "VCC_VDDPAD") (pintype "bidirectional"))
      (node (ref "D98") (pin "VDD") (pinfunction "VCC_VDD") (pintype "bidirectional"))
      (node (ref "D98") (pin "VDDPAD") (pinfunction "VCC_VDDPAD") (pintype "bidirectional"))
      (node (ref "D99") (pin "VDD") (pinfunction "VCC_VDD") (pintype "bidirectional"))
      (node (ref "D99") (pin "VDDPAD") (pinfunction "VCC_VDDPAD") (pintype "bidirectional"))
      (node (ref "J1") (pin "P$2") (pinfunction "2_P$2") (pintype "passive"))
      (node (ref "J4") (pin "P$2") (pinfunction "2_P$2") (pintype "passive"))
    )
    (net (code "2") (name "GND") (class "Default")
      (node (ref "D1") (pin "GND") (pinfunction "GND_GND") (pintype "bidirectional"))
      (node (ref "D1") (pin "GNDPAD") (pinfunction "GND_GNDPAD") (pintype "bidirectional"))
      (node (ref "D10") (pin "GND") (pinfunction "GND_GND") (pintype "bidirectional"))
      (node (ref "D10") (pin "GNDPAD") (pinfunction "GND_GNDPAD") (pintype "bidirectional"))
      (node (ref "D100") (pin "GND") (pinfunction "GND_GND") (pintype "bidirectional"))
      (node (ref "D100") (pin "GNDPAD") (pinfunction "GND_GNDPAD") (pintype "bidirectional"))
      (node (ref "D11") (pin "GND") (pinfunction "GND_GND") (pintype "bidirectional"))
      (node (ref "D11") (pin "GNDPAD") (pinfunction "GND_GNDPAD") (pintype "bidirectional"))
      (node (ref "D12") (pin "GND") (pinfunction "GND_GND") (pintype "bidirectional"))
      (node (ref "D12") (pin "GNDPAD") (pinfunction "GND_GNDPAD") (pintype "bidirectional"))
      (node (ref "D13") (pin "GND") (pinfunction "GND_GND") (pintype "bidirectional"))
      (node (ref "D13") (pin "GNDPAD") (pinfunction "GND_GNDPAD") (pintype "bidirectional"))
      (node (ref "D14") (pin "GND") (pinfunction "GND_GND") (pintype "bidirectional"))
      (node (ref "D14") (pin "GNDPAD") (pinfunction "GND_GNDPAD") (pintype "bidirectional"))
      (node (ref "D15") (pin "GND") (pinfunction "GND_GND") (pintype "bidirectional"))
      (node (ref "D15") (pin "GNDPAD") (pinfunction "GND_GNDPAD") (pintype "bidirectional"))
      (node (ref "D16") (pin "GND") (pinfunction "GND_GND") (pintype "bidirectional"))
      (node (ref "D16") (pin "GNDPAD") (pinfunction "GND_GNDPAD") (pintype "bidirectional"))
      (node (ref "D17") (pin "GND") (pinfunction "GND_GND") (pintype "bidirectional"))
      (node (ref "D17") (pin "GNDPAD") (pinfunction "GND_GNDPAD") (pintype "bidirectional"))
      (node (ref "D18") (pin "GND") (pinfunction "GND_GND") (pintype "bidirectional"))
      (node (ref "D18") (pin "GNDPAD") (pinfunction "GND_GNDPAD") (pintype "bidirectional"))
      (node (ref "D19") (pin "GND") (pinfunction "GND_GND") (pintype "bidirectional"))
      (node (ref "D19") (pin "GNDPAD") (pinfunction "GND_GNDPAD") (pintype "bidirectional"))
      (node (ref "D2") (pin "GND") (pinfunction "GND_GND") (pintype "bidirectional"))
      (node (ref "D2") (pin "GNDPAD") (pinfunction "GND_GNDPAD") (pintype "bidirectional"))
      (node (ref "D20") (pin "GND") (pinfunction "GND_GND") (pintype "bidirectional"))
      (node (ref "D20") (pin "GNDPAD") (pinfunction "GND_GNDPAD") (pintype "bidirectional"))
      (node (ref "D21") (pin "GND") (pinfunction "GND_GND") (pintype "bidirectional"))
      (node (ref "D21") (pin "GNDPAD") (pinfunction "GND_GNDPAD") (pintype "bidirectional"))
      (node (ref "D22") (pin "GND") (pinfunction "GND_GND") (pintype "bidirectional"))
      (node (ref "D22") (pin "GNDPAD") (pinfunction "GND_GNDPAD") (pintype "bidirectional"))
      (node (ref "D23") (pin "GND") (pinfunction "GND_GND") (pintype "bidirectional"))
      (node (ref "D23") (pin "GNDPAD") (pinfunction "GND_GNDPAD") (pintype "bidirectional"))
      (node (ref "D24") (pin "GND") (pinfunction "GND_GND") (pintype "bidirectional"))
      (node (ref "D24") (pin "GNDPAD") (pinfunction "GND_GNDPAD") (pintype "bidirectional"))
      (node (ref "D25") (pin "GND") (pinfunction "GND_GND") (pintype "bidirectional"))
      (node (ref "D25") (pin "GNDPAD") (pinfunction "GND_GNDPAD") (pintype "bidirectional"))
      (node (ref "D26") (pin "GND") (pinfunction "GND_GND") (pintype "bidirectional"))
      (node (ref "D26") (pin "GNDPAD") (pinfunction "GND_GNDPAD") (pintype "bidirectional"))
      (node (ref "D27") (pin "GND") (pinfunction "GND_GND") (pintype "bidirectional"))
      (node (ref "D27") (pin "GNDPAD") (pinfunction "GND_GNDPAD") (pintype "bidirectional"))
      (node (ref "D28") (pin "GND") (pinfunction "GND_GND") (pintype "bidirectional"))
      (node (ref "D28") (pin "GNDPAD") (pinfunction "GND_GNDPAD") (pintype "bidirectional"))
      (node (ref "D29") (pin "GND") (pinfunction "GND_GND") (pintype "bidirectional"))
      (node (ref "D29") (pin "GNDPAD") (pinfunction "GND_GNDPAD") (pintype "bidirectional"))
      (node (ref "D3") (pin "GND") (pinfunction "GND_GND") (pintype "bidirectional"))
      (node (ref "D3") (pin "GNDPAD") (pinfunction "GND_GNDPAD") (pintype "bidirectional"))
      (node (ref "D30") (pin "GND") (pinfunction "GND_GND") (pintype "bidirectional"))
      (node (ref "D30") (pin "GNDPAD") (pinfunction "GND_GNDPAD") (pintype "bidirectional"))
      (node (ref "D31") (pin "GND") (pinfunction "GND_GND") (pintype "bidirectional"))
      (node (ref "D31") (pin "GNDPAD") (pinfunction "GND_GNDPAD") (pintype "bidirectional"))
      (node (ref "D32") (pin "GND") (pinfunction "GND_GND") (pintype "bidirectional"))
      (node (ref "D32") (pin "GNDPAD") (pinfunction "GND_GNDPAD") (pintype "bidirectional"))
      (node (ref "D33") (pin "GND") (pinfunction "GND_GND") (pintype "bidirectional"))
      (node (ref "D33") (pin "GNDPAD") (pinfunction "GND_GNDPAD") (pintype "bidirectional"))
      (node (ref "D34") (pin "GND") (pinfunction "GND_GND") (pintype "bidirectional"))
      (node (ref "D34") (pin "GNDPAD") (pinfunction "GND_GNDPAD") (pintype "bidirectional"))
      (node (ref "D35") (pin "GND") (pinfunction "GND_GND") (pintype "bidirectional"))
      (node (ref "D35") (pin "GNDPAD") (pinfunction "GND_GNDPAD") (pintype "bidirectional"))
      (node (ref "D36") (pin "GND") (pinfunction "GND_GND") (pintype "bidirectional"))
      (node (ref "D36") (pin "GNDPAD") (pinfunction "GND_GNDPAD") (pintype "bidirectional"))
      (node (ref "D37") (pin "GND") (pinfunction "GND_GND") (pintype "bidirectional"))
      (node (ref "D37") (pin "GNDPAD") (pinfunction "GND_GNDPAD") (pintype "bidirectional"))
      (node (ref "D38") (pin "GND") (pinfunction "GND_GND") (pintype "bidirectional"))
      (node (ref "D38") (pin "GNDPAD") (pinfunction "GND_GNDPAD") (pintype "bidirectional"))
      (node (ref "D39") (pin "GND") (pinfunction "GND_GND") (pintype "bidirectional"))
      (node (ref "D39") (pin "GNDPAD") (pinfunction "GND_GNDPAD") (pintype "bidirectional"))
      (node (ref "D4") (pin "GND") (pinfunction "GND_GND") (pintype "bidirectional"))
      (node (ref "D4") (pin "GNDPAD") (pinfunction "GND_GNDPAD") (pintype "bidirectional"))
      (node (ref "D40") (pin "GND") (pinfunction "GND_GND") (pintype "bidirectional"))
      (node (ref "D40") (pin "GNDPAD") (pinfunction "GND_GNDPAD") (pintype "bidirectional"))
      (node (ref "D41") (pin "GND") (pinfunction "GND_GND") (pintype "bidirectional"))
      (node (ref "D41") (pin "GNDPAD") (pinfunction "GND_GNDPAD") (pintype "bidirectional"))
      (node (ref "D42") (pin "GND") (pinfunction "GND_GND") (pintype "bidirectional"))
      (node (ref "D42") (pin "GNDPAD") (pinfunction "GND_GNDPAD") (pintype "bidirectional"))
      (node (ref "D43") (pin "GND") (pinfunction "GND_GND") (pintype "bidirectional"))
      (node (ref "D43") (pin "GNDPAD") (pinfunction "GND_GNDPAD") (pintype "bidirectional"))
      (node (ref "D44") (pin "GND") (pinfunction "GND_GND") (pintype "bidirectional"))
      (node (ref "D44") (pin "GNDPAD") (pinfunction "GND_GNDPAD") (pintype "bidirectional"))
      (node (ref "D45") (pin "GND") (pinfunction "GND_GND") (pintype "bidirectional"))
      (node (ref "D45") (pin "GNDPAD") (pinfunction "GND_GNDPAD") (pintype "bidirectional"))
      (node (ref "D46") (pin "GND") (pinfunction "GND_GND") (pintype "bidirectional"))
      (node (ref "D46") (pin "GNDPAD") (pinfunction "GND_GNDPAD") (pintype "bidirectional"))
      (node (ref "D47") (pin "GND") (pinfunction "GND_GND") (pintype "bidirectional"))
      (node (ref "D47") (pin "GNDPAD") (pinfunction "GND_GNDPAD") (pintype "bidirectional"))
      (node (ref "D48") (pin "GND") (pinfunction "GND_GND") (pintype "bidirectional"))
      (node (ref "D48") (pin "GNDPAD") (pinfunction "GND_GNDPAD") (pintype "bidirectional"))
      (node (ref "D49") (pin "GND") (pinfunction "GND_GND") (pintype "bidirectional"))
      (node (ref "D49") (pin "GNDPAD") (pinfunction "GND_GNDPAD") (pintype "bidirectional"))
      (node (ref "D5") (pin "GND") (pinfunction "GND_GND") (pintype "bidirectional"))
      (node (ref "D5") (pin "GNDPAD") (pinfunction "GND_GNDPAD") (pintype "bidirectional"))
      (node (ref "D50") (pin "GND") (pinfunction "GND_GND") (pintype "bidirectional"))
      (node (ref "D50") (pin "GNDPAD") (pinfunction "GND_GNDPAD") (pintype "bidirectional"))
      (node (ref "D51") (pin "GND") (pinfunction "GND_GND") (pintype "bidirectional"))
      (node (ref "D51") (pin "GNDPAD") (pinfunction "GND_GNDPAD") (pintype "bidirectional"))
      (node (ref "D52") (pin "GND") (pinfunction "GND_GND") (pintype "bidirectional"))
      (node (ref "D52") (pin "GNDPAD") (pinfunction "GND_GNDPAD") (pintype "bidirectional"))
      (node (ref "D53") (pin "GND") (pinfunction "GND_GND") (pintype "bidirectional"))
      (node (ref "D53") (pin "GNDPAD") (pinfunction "GND_GNDPAD") (pintype "bidirectional"))
      (node (ref "D54") (pin "GND") (pinfunction "GND_GND") (pintype "bidirectional"))
      (node (ref "D54") (pin "GNDPAD") (pinfunction "GND_GNDPAD") (pintype "bidirectional"))
      (node (ref "D55") (pin "GND") (pinfunction "GND_GND") (pintype "bidirectional"))
      (node (ref "D55") (pin "GNDPAD") (pinfunction "GND_GNDPAD") (pintype "bidirectional"))
      (node (ref "D56") (pin "GND") (pinfunction "GND_GND") (pintype "bidirectional"))
      (node (ref "D56") (pin "GNDPAD") (pinfunction "GND_GNDPAD") (pintype "bidirectional"))
      (node (ref "D57") (pin "GND") (pinfunction "GND_GND") (pintype "bidirectional"))
      (node (ref "D57") (pin "GNDPAD") (pinfunction "GND_GNDPAD") (pintype "bidirectional"))
      (node (ref "D58") (pin "GND") (pinfunction "GND_GND") (pintype "bidirectional"))
      (node (ref "D58") (pin "GNDPAD") (pinfunction "GND_GNDPAD") (pintype "bidirectional"))
      (node (ref "D59") (pin "GND") (pinfunction "GND_GND") (pintype "bidirectional"))
      (node (ref "D59") (pin "GNDPAD") (pinfunction "GND_GNDPAD") (pintype "bidirectional"))
      (node (ref "D6") (pin "GND") (pinfunction "GND_GND") (pintype "bidirectional"))
      (node (ref "D6") (pin "GNDPAD") (pinfunction "GND_GNDPAD") (pintype "bidirectional"))
      (node (ref "D60") (pin "GND") (pinfunction "GND_GND") (pintype "bidirectional"))
      (node (ref "D60") (pin "GNDPAD") (pinfunction "GND_GNDPAD") (pintype "bidirectional"))
      (node (ref "D61") (pin "GND") (pinfunction "GND_GND") (pintype "bidirectional"))
      (node (ref "D61") (pin "GNDPAD") (pinfunction "GND_GNDPAD") (pintype "bidirectional"))
      (node (ref "D62") (pin "GND") (pinfunction "GND_GND") (pintype "bidirectional"))
      (node (ref "D62") (pin "GNDPAD") (pinfunction "GND_GNDPAD") (pintype "bidirectional"))
      (node (ref "D63") (pin "GND") (pinfunction "GND_GND") (pintype "bidirectional"))
      (node (ref "D63") (pin "GNDPAD") (pinfunction "GND_GNDPAD") (pintype "bidirectional"))
      (node (ref "D64") (pin "GND") (pinfunction "GND_GND") (pintype "bidirectional"))
      (node (ref "D64") (pin "GNDPAD") (pinfunction "GND_GNDPAD") (pintype "bidirectional"))
      (node (ref "D65") (pin "GND") (pinfunction "GND_GND") (pintype "bidirectional"))
      (node (ref "D65") (pin "GNDPAD") (pinfunction "GND_GNDPAD") (pintype "bidirectional"))
      (node (ref "D66") (pin "GND") (pinfunction "GND_GND") (pintype "bidirectional"))
      (node (ref "D66") (pin "GNDPAD") (pinfunction "GND_GNDPAD") (pintype "bidirectional"))
      (node (ref "D67") (pin "GND") (pinfunction "GND_GND") (pintype "bidirectional"))
      (node (ref "D67") (pin "GNDPAD") (pinfunction "GND_GNDPAD") (pintype "bidirectional"))
      (node (ref "D68") (pin "GND") (pinfunction "GND_GND") (pintype "bidirectional"))
      (node (ref "D68") (pin "GNDPAD") (pinfunction "GND_GNDPAD") (pintype "bidirectional"))
      (node (ref "D69") (pin "GND") (pinfunction "GND_GND") (pintype "bidirectional"))
      (node (ref "D69") (pin "GNDPAD") (pinfunction "GND_GNDPAD") (pintype "bidirectional"))
      (node (ref "D7") (pin "GND") (pinfunction "GND_GND") (pintype "bidirectional"))
      (node (ref "D7") (pin "GNDPAD") (pinfunction "GND_GNDPAD") (pintype "bidirectional"))
      (node (ref "D70") (pin "GND") (pinfunction "GND_GND") (pintype "bidirectional"))
      (node (ref "D70") (pin "GNDPAD") (pinfunction "GND_GNDPAD") (pintype "bidirectional"))
      (node (ref "D71") (pin "GND") (pinfunction "GND_GND") (pintype "bidirectional"))
      (node (ref "D71") (pin "GNDPAD") (pinfunction "GND_GNDPAD") (pintype "bidirectional"))
      (node (ref "D72") (pin "GND") (pinfunction "GND_GND") (pintype "bidirectional"))
      (node (ref "D72") (pin "GNDPAD") (pinfunction "GND_GNDPAD") (pintype "bidirectional"))
      (node (ref "D73") (pin "GND") (pinfunction "GND_GND") (pintype "bidirectional"))
      (node (ref "D73") (pin "GNDPAD") (pinfunction "GND_GNDPAD") (pintype "bidirectional"))
      (node (ref "D74") (pin "GND") (pinfunction "GND_GND") (pintype "bidirectional"))
      (node (ref "D74") (pin "GNDPAD") (pinfunction "GND_GNDPAD") (pintype "bidirectional"))
      (node (ref "D75") (pin "GND") (pinfunction "GND_GND") (pintype "bidirectional"))
      (node (ref "D75") (pin "GNDPAD") (pinfunction "GND_GNDPAD") (pintype "bidirectional"))
      (node (ref "D76") (pin "GND") (pinfunction "GND_GND") (pintype "bidirectional"))
      (node (ref "D76") (pin "GNDPAD") (pinfunction "GND_GNDPAD") (pintype "bidirectional"))
      (node (ref "D77") (pin "GND") (pinfunction "GND_GND") (pintype "bidirectional"))
      (node (ref "D77") (pin "GNDPAD") (pinfunction "GND_GNDPAD") (pintype "bidirectional"))
      (node (ref "D78") (pin "GND") (pinfunction "GND_GND") (pintype "bidirectional"))
      (node (ref "D78") (pin "GNDPAD") (pinfunction "GND_GNDPAD") (pintype "bidirectional"))
      (node (ref "D79") (pin "GND") (pinfunction "GND_GND") (pintype "bidirectional"))
      (node (ref "D79") (pin "GNDPAD") (pinfunction "GND_GNDPAD") (pintype "bidirectional"))
      (node (ref "D8") (pin "GND") (pinfunction "GND_GND") (pintype "bidirectional"))
      (node (ref "D8") (pin "GNDPAD") (pinfunction "GND_GNDPAD") (pintype "bidirectional"))
      (node (ref "D80") (pin "GND") (pinfunction "GND_GND") (pintype "bidirectional"))
      (node (ref "D80") (pin "GNDPAD") (pinfunction "GND_GNDPAD") (pintype "bidirectional"))
      (node (ref "D81") (pin "GND") (pinfunction "GND_GND") (pintype "bidirectional"))
      (node (ref "D81") (pin "GNDPAD") (pinfunction "GND_GNDPAD") (pintype "bidirectional"))
      (node (ref "D82") (pin "GND") (pinfunction "GND_GND") (pintype "bidirectional"))
      (node (ref "D82") (pin "GNDPAD") (pinfunction "GND_GNDPAD") (pintype "bidirectional"))
      (node (ref "D83") (pin "GND") (pinfunction "GND_GND") (pintype "bidirectional"))
      (node (ref "D83") (pin "GNDPAD") (pinfunction "GND_GNDPAD") (pintype "bidirectional"))
      (node (ref "D84") (pin "GND") (pinfunction "GND_GND") (pintype "bidirectional"))
      (node (ref "D84") (pin "GNDPAD") (pinfunction "GND_GNDPAD") (pintype "bidirectional"))
      (node (ref "D85") (pin "GND") (pinfunction "GND_GND") (pintype "bidirectional"))
      (node (ref "D85") (pin "GNDPAD") (pinfunction "GND_GNDPAD") (pintype "bidirectional"))
      (node (ref "D86") (pin "GND") (pinfunction "GND_GND") (pintype "bidirectional"))
      (node (ref "D86") (pin "GNDPAD") (pinfunction "GND_GNDPAD") (pintype "bidirectional"))
      (node (ref "D87") (pin "GND") (pinfunction "GND_GND") (pintype "bidirectional"))
      (node (ref "D87") (pin "GNDPAD") (pinfunction "GND_GNDPAD") (pintype "bidirectional"))
      (node (ref "D88") (pin "GND") (pinfunction "GND_GND") (pintype "bidirectional"))
      (node (ref "D88") (pin "GNDPAD") (pinfunction "GND_GNDPAD") (pintype "bidirectional"))
      (node (ref "D89") (pin "GND") (pinfunction "GND_GND") (pintype "bidirectional"))
      (node (ref "D89") (pin "GNDPAD") (pinfunction "GND_GNDPAD") (pintype "bidirectional"))
      (node (ref "D9") (pin "GND") (pinfunction "GND_GND") (pintype "bidirectional"))
      (node (ref "D9") (pin "GNDPAD") (pinfunction "GND_GNDPAD") (pintype "bidirectional"))
      (node (ref "D90") (pin "GND") (pinfunction "GND_GND") (pintype "bidirectional"))
      (node (ref "D90") (pin "GNDPAD") (pinfunction "GND_GNDPAD") (pintype "bidirectional"))
      (node (ref "D91") (pin "GND") (pinfunction "GND_GND") (pintype "bidirectional"))
      (node (ref "D91") (pin "GNDPAD") (pinfunction "GND_GNDPAD") (pintype "bidirectional"))
      (node (ref "D92") (pin "GND") (pinfunction "GND_GND") (pintype "bidirectional"))
      (node (ref "D92") (pin "GNDPAD") (pinfunction "GND_GNDPAD") (pintype "bidirectional"))
      (node (ref "D93") (pin "GND") (pinfunction "GND_GND") (pintype "bidirectional"))
      (node (ref "D93") (pin "GNDPAD") (pinfunction "GND_GNDPAD") (pintype "bidirectional"))
      (node (ref "D94") (pin "GND") (pinfunction "GND_GND") (pintype "bidirectional"))
      (node (ref "D94") (pin "GNDPAD") (pinfunction "GND_GNDPAD") (pintype "bidirectional"))
      (node (ref "D95") (pin "GND") (pinfunction "GND_GND") (pintype "bidirectional"))
      (node (ref "D95") (pin "GNDPAD") (pinfunction "GND_GNDPAD") (pintype "bidirectional"))
      (node (ref "D96") (pin "GND") (pinfunction "GND_GND") (pintype "bidirectional"))
      (node (ref "D96") (pin "GNDPAD") (pinfunction "GND_GNDPAD") (pintype "bidirectional"))
      (node (ref "D97") (pin "GND") (pinfunction "GND_GND") (pintype "bidirectional"))
      (node (ref "D97") (pin "GNDPAD") (pinfunction "GND_GNDPAD") (pintype "bidirectional"))
      (node (ref "D98") (pin "GND") (pinfunction "GND_GND") (pintype "bidirectional"))
      (node (ref "D98") (pin "GNDPAD") (pinfunction "GND_GNDPAD") (pintype "bidirectional"))
      (node (ref "D99") (pin "GND") (pinfunction "GND_GND") (pintype "bidirectional"))
      (node (ref "D99") (pin "GNDPAD") (pinfunction "GND_GNDPAD") (pintype "bidirectional"))
      (node (ref "J1") (pin "P$1") (pinfunction "1_P$1") (pintype "passive"))
      (node (ref "J4") (pin "P$1") (pinfunction "1_P$1") (pintype "passive"))
    )
    (net (code "3") (name "Net-(D1-CI)") (class "Default")
      (node (ref "D1") (pin "CKI") (pinfunction "CI_CKI") (pintype "bidirectional"))
      (node (ref "J2") (pin "P$2") (pinfunction "2_P$2") (pintype "passive"))
    )
    (net (code "4") (name "Net-(D1-CO)") (class "Default")
      (node (ref "D1") (pin "CKO") (pinfunction "CO_CKO") (pintype "bidirectional"))
      (node (ref "D2") (pin "CKI") (pinfunction "CI_CKI") (pintype "bidirectional"))
    )
    (net (code "5") (name "Net-(D1-DI)") (class "Default")
      (node (ref "D1") (pin "SDI") (pinfunction "DI_SDI") (pintype "bidirectional"))
      (node (ref "J2") (pin "P$1") (pinfunction "1_P$1") (pintype "passive"))
    )
    (net (code "6") (name "Net-(D1-DO)") (class "Default")
      (node (ref "D1") (pin "SDO") (pinfunction "DO_SDO") (pintype "bidirectional"))
      (node (ref "D2") (pin "SDI") (pinfunction "DI_SDI") (pintype "bidirectional"))
    )
    (net (code "7") (name "Net-(D2-CO)") (class "Default")
      (node (ref "D2") (pin "CKO") (pinfunction "CO_CKO") (pintype "bidirectional"))
      (node (ref "D3") (pin "CKI") (pinfunction "CI_CKI") (pintype "bidirectional"))
    )
    (net (code "8") (name "Net-(D2-DO)") (class "Default")
      (node (ref "D2") (pin "SDO") (pinfunction "DO_SDO") (pintype "bidirectional"))
      (node (ref "D3") (pin "SDI") (pinfunction "DI_SDI") (pintype "bidirectional"))
    )
    (net (code "9") (name "Net-(D3-CO)") (class "Default")
      (node (ref "D3") (pin "CKO") (pinfunction "CO_CKO") (pintype "bidirectional"))
      (node (ref "D4") (pin "CKI") (pinfunction "CI_CKI") (pintype "bidirectional"))
    )
    (net (code "10") (name "Net-(D3-DO)") (class "Default")
      (node (ref "D3") (pin "SDO") (pinfunction "DO_SDO") (pintype "bidirectional"))
      (node (ref "D4") (pin "SDI") (pinfunction "DI_SDI") (pintype "bidirectional"))
    )
    (net (code "11") (name "Net-(D4-CO)") (class "Default")
      (node (ref "D4") (pin "CKO") (pinfunction "CO_CKO") (pintype "bidirectional"))
      (node (ref "D5") (pin "CKI") (pinfunction "CI_CKI") (pintype "bidirectional"))
    )
    (net (code "12") (name "Net-(D4-DO)") (class "Default")
      (node (ref "D4") (pin "SDO") (pinfunction "DO_SDO") (pintype "bidirectional"))
      (node (ref "D5") (pin "SDI") (pinfunction "DI_SDI") (pintype "bidirectional"))
    )
    (net (code "13") (name "Net-(D5-CO)") (class "Default")
      (node (ref "D5") (pin "CKO") (pinfunction "CO_CKO") (pintype "bidirectional"))
      (node (ref "D6") (pin "CKI") (pinfunction "CI_CKI") (pintype "bidirectional"))
    )
    (net (code "14") (name "Net-(D5-DO)") (class "Default")
      (node (ref "D5") (pin "SDO") (pinfunction "DO_SDO") (pintype "bidirectional"))
      (node (ref "D6") (pin "SDI") (pinfunction "DI_SDI") (pintype "bidirectional"))
    )
    (net (code "15") (name "Net-(D6-CO)") (class "Default")
      (node (ref "D6") (pin "CKO") (pinfunction "CO_CKO") (pintype "bidirectional"))
      (node (ref "D7") (pin "CKI") (pinfunction "CI_CKI") (pintype "bidirectional"))
    )
    (net (code "16") (name "Net-(D6-DO)") (class "Default")
      (node (ref "D6") (pin "SDO") (pinfunction "DO_SDO") (pintype "bidirectional"))
      (node (ref "D7") (pin "SDI") (pinfunction "DI_SDI") (pintype "bidirectional"))
    )
    (net (code "17") (name "Net-(D7-CO)") (class "Default")
      (node (ref "D7") (pin "CKO") (pinfunction "CO_CKO") (pintype "bidirectional"))
      (node (ref "D8") (pin "CKI") (pinfunction "CI_CKI") (pintype "bidirectional"))
    )
    (net (code "18") (name "Net-(D7-DO)") (class "Default")
      (node (ref "D7") (pin "SDO") (pinfunction "DO_SDO") (pintype "bidirectional"))
      (node (ref "D8") (pin "SDI") (pinfunction "DI_SDI") (pintype "bidirectional"))
    )
    (net (code "19") (name "Net-(D8-CO)") (class "Default")
      (node (ref "D8") (pin "CKO") (pinfunction "CO_CKO") (pintype "bidirectional"))
      (node (ref "D9") (pin "CKI") (pinfunction "CI_CKI") (pintype "bidirectional"))
    )
    (net (code "20") (name "Net-(D8-DO)") (class "Default")
      (node (ref "D8") (pin "SDO") (pinfunction "DO_SDO") (pintype "bidirectional"))
      (node (ref "D9") (pin "SDI") (pinfunction "DI_SDI") (pintype "bidirectional"))
    )
    (net (code "21") (name "Net-(D10-CI)") (class "Default")
      (node (ref "D10") (pin "CKI") (pinfunction "CI_CKI") (pintype "bidirectional"))
      (node (ref "D9") (pin "CKO") (pinfunction "CO_CKO") (pintype "bidirectional"))
    )
    (net (code "22") (name "Net-(D10-CO)") (class "Default")
      (node (ref "D10") (pin "CKO") (pinfunction "CO_CKO") (pintype "bidirectional"))
      (node (ref "D11") (pin "CKI") (pinfunction "CI_CKI") (pintype "bidirectional"))
    )
    (net (code "23") (name "Net-(D10-DI)") (class "Default")
      (node (ref "D10") (pin "SDI") (pinfunction "DI_SDI") (pintype "bidirectional"))
      (node (ref "D9") (pin "SDO") (pinfunction "DO_SDO") (pintype "bidirectional"))
    )
    (net (code "24") (name "Net-(D10-DO)") (class "Default")
      (node (ref "D10") (pin "SDO") (pinfunction "DO_SDO") (pintype "bidirectional"))
      (node (ref "D11") (pin "SDI") (pinfunction "DI_SDI") (pintype "bidirectional"))
    )
    (net (code "25") (name "Net-(D11-CO)") (class "Default")
      (node (ref "D11") (pin "CKO") (pinfunction "CO_CKO") (pintype "bidirectional"))
      (node (ref "D12") (pin "CKI") (pinfunction "CI_CKI") (pintype "bidirectional"))
    )
    (net (code "26") (name "Net-(D11-DO)") (class "Default")
      (node (ref "D11") (pin "SDO") (pinfunction "DO_SDO") (pintype "bidirectional"))
      (node (ref "D12") (pin "SDI") (pinfunction "DI_SDI") (pintype "bidirectional"))
    )
    (net (code "27") (name "Net-(D12-CO)") (class "Default")
      (node (ref "D12") (pin "CKO") (pinfunction "CO_CKO") (pintype "bidirectional"))
      (node (ref "D13") (pin "CKI") (pinfunction "CI_CKI") (pintype "bidirectional"))
    )
    (net (code "28") (name "Net-(D12-DO)") (class "Default")
      (node (ref "D12") (pin "SDO") (pinfunction "DO_SDO") (pintype "bidirectional"))
      (node (ref "D13") (pin "SDI") (pinfunction "DI_SDI") (pintype "bidirectional"))
    )
    (net (code "29") (name "Net-(D13-CO)") (class "Default")
      (node (ref "D13") (pin "CKO") (pinfunction "CO_CKO") (pintype "bidirectional"))
      (node (ref "D14") (pin "CKI") (pinfunction "CI_CKI") (pintype "bidirectional"))
    )
    (net (code "30") (name "Net-(D13-DO)") (class "Default")
      (node (ref "D13") (pin "SDO") (pinfunction "DO_SDO") (pintype "bidirectional"))
      (node (ref "D14") (pin "SDI") (pinfunction "DI_SDI") (pintype "bidirectional"))
    )
    (net (code "31") (name "Net-(D14-CO)") (class "Default")
      (node (ref "D14") (pin "CKO") (pinfunction "CO_CKO") (pintype "bidirectional"))
      (node (ref "D15") (pin "CKI") (pinfunction "CI_CKI") (pintype "bidirectional"))
    )
    (net (code "32") (name "Net-(D14-DO)") (class "Default")
      (node (ref "D14") (pin "SDO") (pinfunction "DO_SDO") (pintype "bidirectional"))
      (node (ref "D15") (pin "SDI") (pinfunction "DI_SDI") (pintype "bidirectional"))
    )
    (net (code "33") (name "Net-(D15-CO)") (class "Default")
      (node (ref "D15") (pin "CKO") (pinfunction "CO_CKO") (pintype "bidirectional"))
      (node (ref "D16") (pin "CKI") (pinfunction "CI_CKI") (pintype "bidirectional"))
    )
    (net (code "34") (name "Net-(D15-DO)") (class "Default")
      (node (ref "D15") (pin "SDO") (pinfunction "DO_SDO") (pintype "bidirectional"))
      (node (ref "D16") (pin "SDI") (pinfunction "DI_SDI") (pintype "bidirectional"))
    )
    (net (code "35") (name "Net-(D16-CO)") (class "Default")
      (node (ref "D16") (pin "CKO") (pinfunction "CO_CKO") (pintype "bidirectional"))
      (node (ref "D17") (pin "CKI") (pinfunction "CI_CKI") (pintype "bidirectional"))
    )
    (net (code "36") (name "Net-(D16-DO)") (class "Default")
      (node (ref "D16") (pin "SDO") (pinfunction "DO_SDO") (pintype "bidirectional"))
      (node (ref "D17") (pin "SDI") (pinfunction "DI_SDI") (pintype "bidirectional"))
    )
    (net (code "37") (name "Net-(D17-CO)") (class "Default")
      (node (ref "D17") (pin "CKO") (pinfunction "CO_CKO") (pintype "bidirectional"))
      (node (ref "D18") (pin "CKI") (pinfunction "CI_CKI") (pintype "bidirectional"))
    )
    (net (code "38") (name "Net-(D17-DO)") (class "Default")
      (node (ref "D17") (pin "SDO") (pinfunction "DO_SDO") (pintype "bidirectional"))
      (node (ref "D18") (pin "SDI") (pinfunction "DI_SDI") (pintype "bidirectional"))
    )
    (net (code "39") (name "Net-(D18-CO)") (class "Default")
      (node (ref "D18") (pin "CKO") (pinfunction "CO_CKO") (pintype "bidirectional"))
      (node (ref "D19") (pin "CKI") (pinfunction "CI_CKI") (pintype "bidirectional"))
    )
    (net (code "40") (name "Net-(D18-DO)") (class "Default")
      (node (ref "D18") (pin "SDO") (pinfunction "DO_SDO") (pintype "bidirectional"))
      (node (ref "D19") (pin "SDI") (pinfunction "DI_SDI") (pintype "bidirectional"))
    )
    (net (code "41") (name "Net-(D19-CO)") (class "Default")
      (node (ref "D19") (pin "CKO") (pinfunction "CO_CKO") (pintype "bidirectional"))
      (node (ref "D20") (pin "CKI") (pinfunction "CI_CKI") (pintype "bidirectional"))
    )
    (net (code "42") (name "Net-(D19-DO)") (class "Default")
      (node (ref "D19") (pin "SDO") (pinfunction "DO_SDO") (pintype "bidirectional"))
      (node (ref "D20") (pin "SDI") (pinfunction "DI_SDI") (pintype "bidirectional"))
    )
    (net (code "43") (name "Net-(D20-CO)") (class "Default")
      (node (ref "D20") (pin "CKO") (pinfunction "CO_CKO") (pintype "bidirectional"))
      (node (ref "D21") (pin "CKI") (pinfunction "CI_CKI") (pintype "bidirectional"))
    )
    (net (code "44") (name "Net-(D20-DO)") (class "Default")
      (node (ref "D20") (pin "SDO") (pinfunction "DO_SDO") (pintype "bidirectional"))
      (node (ref "D21") (pin "SDI") (pinfunction "DI_SDI") (pintype "bidirectional"))
    )
    (net (code "45") (name "Net-(D21-CO)") (class "Default")
      (node (ref "D21") (pin "CKO") (pinfunction "CO_CKO") (pintype "bidirectional"))
      (node (ref "D22") (pin "CKI") (pinfunction "CI_CKI") (pintype "bidirectional"))
    )
    (net (code "46") (name "Net-(D21-DO)") (class "Default")
      (node (ref "D21") (pin "SDO") (pinfunction "DO_SDO") (pintype "bidirectional"))
      (node (ref "D22") (pin "SDI") (pinfunction "DI_SDI") (pintype "bidirectional"))
    )
    (net (code "47") (name "Net-(D22-CO)") (class "Default")
      (node (ref "D22") (pin "CKO") (pinfunction "CO_CKO") (pintype "bidirectional"))
      (node (ref "D23") (pin "CKI") (pinfunction "CI_CKI") (pintype "bidirectional"))
    )
    (net (code "48") (name "Net-(D22-DO)") (class "Default")
      (node (ref "D22") (pin "SDO") (pinfunction "DO_SDO") (pintype "bidirectional"))
      (node (ref "D23") (pin "SDI") (pinfunction "DI_SDI") (pintype "bidirectional"))
    )
    (net (code "49") (name "Net-(D23-CO)") (class "Default")
      (node (ref "D23") (pin "CKO") (pinfunction "CO_CKO") (pintype "bidirectional"))
      (node (ref "D24") (pin "CKI") (pinfunction "CI_CKI") (pintype "bidirectional"))
    )
    (net (code "50") (name "Net-(D23-DO)") (class "Default")
      (node (ref "D23") (pin "SDO") (pinfunction "DO_SDO") (pintype "bidirectional"))
      (node (ref "D24") (pin "SDI") (pinfunction "DI_SDI") (pintype "bidirectional"))
    )
    (net (code "51") (name "Net-(D24-CO)") (class "Default")
      (node (ref "D24") (pin "CKO") (pinfunction "CO_CKO") (pintype "bidirectional"))
      (node (ref "D25") (pin "CKI") (pinfunction "CI_CKI") (pintype "bidirectional"))
    )
    (net (code "52") (name "Net-(D24-DO)") (class "Default")
      (node (ref "D24") (pin "SDO") (pinfunction "DO_SDO") (pintype "bidirectional"))
      (node (ref "D25") (pin "SDI") (pinfunction "DI_SDI") (pintype "bidirectional"))
    )
    (net (code "53") (name "Net-(D25-CO)") (class "Default")
      (node (ref "D25") (pin "CKO") (pinfunction "CO_CKO") (pintype "bidirectional"))
      (node (ref "D26") (pin "CKI") (pinfunction "CI_CKI") (pintype "bidirectional"))
    )
    (net (code "54") (name "Net-(D25-DO)") (class "Default")
      (node (ref "D25") (pin "SDO") (pinfunction "DO_SDO") (pintype "bidirectional"))
      (node (ref "D26") (pin "SDI") (pinfunction "DI_SDI") (pintype "bidirectional"))
    )
    (net (code "55") (name "Net-(D26-CO)") (class "Default")
      (node (ref "D26") (pin "CKO") (pinfunction "CO_CKO") (pintype "bidirectional"))
      (node (ref "D27") (pin "CKI") (pinfunction "CI_CKI") (pintype "bidirectional"))
    )
    (net (code "56") (name "Net-(D26-DO)") (class "Default")
      (node (ref "D26") (pin "SDO") (pinfunction "DO_SDO") (pintype "bidirectional"))
      (node (ref "D27") (pin "SDI") (pinfunction "DI_SDI") (pintype "bidirectional"))
    )
    (net (code "57") (name "Net-(D27-CO)") (class "Default")
      (node (ref "D27") (pin "CKO") (pinfunction "CO_CKO") (pintype "bidirectional"))
      (node (ref "D28") (pin "CKI") (pinfunction "CI_CKI") (pintype "bidirectional"))
    )
    (net (code "58") (name "Net-(D27-DO)") (class "Default")
      (node (ref "D27") (pin "SDO") (pinfunction "DO_SDO") (pintype "bidirectional"))
      (node (ref "D28") (pin "SDI") (pinfunction "DI_SDI") (pintype "bidirectional"))
    )
    (net (code "59") (name "Net-(D28-CO)") (class "Default")
      (node (ref "D28") (pin "CKO") (pinfunction "CO_CKO") (pintype "bidirectional"))
      (node (ref "D29") (pin "CKI") (pinfunction "CI_CKI") (pintype "bidirectional"))
    )
    (net (code "60") (name "Net-(D28-DO)") (class "Default")
      (node (ref "D28") (pin "SDO") (pinfunction "DO_SDO") (pintype "bidirectional"))
      (node (ref "D29") (pin "SDI") (pinfunction "DI_SDI") (pintype "bidirectional"))
    )
    (net (code "61") (name "Net-(D29-CO)") (class "Default")
      (node (ref "D29") (pin "CKO") (pinfunction "CO_CKO") (pintype "bidirectional"))
      (node (ref "D30") (pin "CKI") (pinfunction "CI_CKI") (pintype "bidirectional"))
    )
    (net (code "62") (name "Net-(D29-DO)") (class "Default")
      (node (ref "D29") (pin "SDO") (pinfunction "DO_SDO") (pintype "bidirectional"))
      (node (ref "D30") (pin "SDI") (pinfunction "DI_SDI") (pintype "bidirectional"))
    )
    (net (code "63") (name "Net-(D30-CO)") (class "Default")
      (node (ref "D30") (pin "CKO") (pinfunction "CO_CKO") (pintype "bidirectional"))
      (node (ref "D31") (pin "CKI") (pinfunction "CI_CKI") (pintype "bidirectional"))
    )
    (net (code "64") (name "Net-(D30-DO)") (class "Default")
      (node (ref "D30") (pin "SDO") (pinfunction "DO_SDO") (pintype "bidirectional"))
      (node (ref "D31") (pin "SDI") (pinfunction "DI_SDI") (pintype "bidirectional"))
    )
    (net (code "65") (name "Net-(D31-CO)") (class "Default")
      (node (ref "D31") (pin "CKO") (pinfunction "CO_CKO") (pintype "bidirectional"))
      (node (ref "D32") (pin "CKI") (pinfunction "CI_CKI") (pintype "bidirectional"))
    )
    (net (code "66") (name "Net-(D31-DO)") (class "Default")
      (node (ref "D31") (pin "SDO") (pinfunction "DO_SDO") (pintype "bidirectional"))
      (node (ref "D32") (pin "SDI") (pinfunction "DI_SDI") (pintype "bidirectional"))
    )
    (net (code "67") (name "Net-(D32-CO)") (class "Default")
      (node (ref "D32") (pin "CKO") (pinfunction "CO_CKO") (pintype "bidirectional"))
      (node (ref "D33") (pin "CKI") (pinfunction "CI_CKI") (pintype "bidirectional"))
    )
    (net (code "68") (name "Net-(D32-DO)") (class "Default")
      (node (ref "D32") (pin "SDO") (pinfunction "DO_SDO") (pintype "bidirectional"))
      (node (ref "D33") (pin "SDI") (pinfunction "DI_SDI") (pintype "bidirectional"))
    )
    (net (code "69") (name "Net-(D33-CO)") (class "Default")
      (node (ref "D33") (pin "CKO") (pinfunction "CO_CKO") (pintype "bidirectional"))
      (node (ref "D34") (pin "CKI") (pinfunction "CI_CKI") (pintype "bidirectional"))
    )
    (net (code "70") (name "Net-(D33-DO)") (class "Default")
      (node (ref "D33") (pin "SDO") (pinfunction "DO_SDO") (pintype "bidirectional"))
      (node (ref "D34") (pin "SDI") (pinfunction "DI_SDI") (pintype "bidirectional"))
    )
    (net (code "71") (name "Net-(D34-CO)") (class "Default")
      (node (ref "D34") (pin "CKO") (pinfunction "CO_CKO") (pintype "bidirectional"))
      (node (ref "D35") (pin "CKI") (pinfunction "CI_CKI") (pintype "bidirectional"))
    )
    (net (code "72") (name "Net-(D34-DO)") (class "Default")
      (node (ref "D34") (pin "SDO") (pinfunction "DO_SDO") (pintype "bidirectional"))
      (node (ref "D35") (pin "SDI") (pinfunction "DI_SDI") (pintype "bidirectional"))
    )
    (net (code "73") (name "Net-(D35-CO)") (class "Default")
      (node (ref "D35") (pin "CKO") (pinfunction "CO_CKO") (pintype "bidirectional"))
      (node (ref "D36") (pin "CKI") (pinfunction "CI_CKI") (pintype "bidirectional"))
    )
    (net (code "74") (name "Net-(D35-DO)") (class "Default")
      (node (ref "D35") (pin "SDO") (pinfunction "DO_SDO") (pintype "bidirectional"))
      (node (ref "D36") (pin "SDI") (pinfunction "DI_SDI") (pintype "bidirectional"))
    )
    (net (code "75") (name "Net-(D36-CO)") (class "Default")
      (node (ref "D36") (pin "CKO") (pinfunction "CO_CKO") (pintype "bidirectional"))
      (node (ref "D37") (pin "CKI") (pinfunction "CI_CKI") (pintype "bidirectional"))
    )
    (net (code "76") (name "Net-(D36-DO)") (class "Default")
      (node (ref "D36") (pin "SDO") (pinfunction "DO_SDO") (pintype "bidirectional"))
      (node (ref "D37") (pin "SDI") (pinfunction "DI_SDI") (pintype "bidirectional"))
    )
    (net (code "77") (name "Net-(D37-CO)") (class "Default")
      (node (ref "D37") (pin "CKO") (pinfunction "CO_CKO") (pintype "bidirectional"))
      (node (ref "D38") (pin "CKI") (pinfunction "CI_CKI") (pintype "bidirectional"))
    )
    (net (code "78") (name "Net-(D37-DO)") (class "Default")
      (node (ref "D37") (pin "SDO") (pinfunction "DO_SDO") (pintype "bidirectional"))
      (node (ref "D38") (pin "SDI") (pinfunction "DI_SDI") (pintype "bidirectional"))
    )
    (net (code "79") (name "Net-(D38-CO)") (class "Default")
      (node (ref "D38") (pin "CKO") (pinfunction "CO_CKO") (pintype "bidirectional"))
      (node (ref "D39") (pin "CKI") (pinfunction "CI_CKI") (pintype "bidirectional"))
    )
    (net (code "80") (name "Net-(D38-DO)") (class "Default")
      (node (ref "D38") (pin "SDO") (pinfunction "DO_SDO") (pintype "bidirectional"))
      (node (ref "D39") (pin "SDI") (pinfunction "DI_SDI") (pintype "bidirectional"))
    )
    (net (code "81") (name "Net-(D39-CO)") (class "Default")
      (node (ref "D39") (pin "CKO") (pinfunction "CO_CKO") (pintype "bidirectional"))
      (node (ref "D40") (pin "CKI") (pinfunction "CI_CKI") (pintype "bidirectional"))
    )
    (net (code "82") (name "Net-(D39-DO)") (class "Default")
      (node (ref "D39") (pin "SDO") (pinfunction "DO_SDO") (pintype "bidirectional"))
      (node (ref "D40") (pin "SDI") (pinfunction "DI_SDI") (pintype "bidirectional"))
    )
    (net (code "83") (name "Net-(D40-CO)") (class "Default")
      (node (ref "D40") (pin "CKO") (pinfunction "CO_CKO") (pintype "bidirectional"))
      (node (ref "D41") (pin "CKI") (pinfunction "CI_CKI") (pintype "bidirectional"))
    )
    (net (code "84") (name "Net-(D40-DO)") (class "Default")
      (node (ref "D40") (pin "SDO") (pinfunction "DO_SDO") (pintype "bidirectional"))
      (node (ref "D41") (pin "SDI") (pinfunction "DI_SDI") (pintype "bidirectional"))
    )
    (net (code "85") (name "Net-(D41-CO)") (class "Default")
      (node (ref "D41") (pin "CKO") (pinfunction "CO_CKO") (pintype "bidirectional"))
      (node (ref "D42") (pin "CKI") (pinfunction "CI_CKI") (pintype "bidirectional"))
    )
    (net (code "86") (name "Net-(D41-DO)") (class "Default")
      (node (ref "D41") (pin "SDO") (pinfunction "DO_SDO") (pintype "bidirectional"))
      (node (ref "D42") (pin "SDI") (pinfunction "DI_SDI") (pintype "bidirectional"))
    )
    (net (code "87") (name "Net-(D42-CO)") (class "Default")
      (node (ref "D42") (pin "CKO") (pinfunction "CO_CKO") (pintype "bidirectional"))
      (node (ref "D43") (pin "CKI") (pinfunction "CI_CKI") (pintype "bidirectional"))
    )
    (net (code "88") (name "Net-(D42-DO)") (class "Default")
      (node (ref "D42") (pin "SDO") (pinfunction "DO_SDO") (pintype "bidirectional"))
      (node (ref "D43") (pin "SDI") (pinfunction "DI_SDI") (pintype "bidirectional"))
    )
    (net (code "89") (name "Net-(D43-CO)") (class "Default")
      (node (ref "D43") (pin "CKO") (pinfunction "CO_CKO") (pintype "bidirectional"))
      (node (ref "D44") (pin "CKI") (pinfunction "CI_CKI") (pintype "bidirectional"))
    )
    (net (code "90") (name "Net-(D43-DO)") (class "Default")
      (node (ref "D43") (pin "SDO") (pinfunction "DO_SDO") (pintype "bidirectional"))
      (node (ref "D44") (pin "SDI") (pinfunction "DI_SDI") (pintype "bidirectional"))
    )
    (net (code "91") (name "Net-(D44-CO)") (class "Default")
      (node (ref "D44") (pin "CKO") (pinfunction "CO_CKO") (pintype "bidirectional"))
      (node (ref "D45") (pin "CKI") (pinfunction "CI_CKI") (pintype "bidirectional"))
    )
    (net (code "92") (name "Net-(D44-DO)") (class "Default")
      (node (ref "D44") (pin "SDO") (pinfunction "DO_SDO") (pintype "bidirectional"))
      (node (ref "D45") (pin "SDI") (pinfunction "DI_SDI") (pintype "bidirectional"))
    )
    (net (code "93") (name "Net-(D45-CO)") (class "Default")
      (node (ref "D45") (pin "CKO") (pinfunction "CO_CKO") (pintype "bidirectional"))
      (node (ref "D46") (pin "CKI") (pinfunction "CI_CKI") (pintype "bidirectional"))
    )
    (net (code "94") (name "Net-(D45-DO)") (class "Default")
      (node (ref "D45") (pin "SDO") (pinfunction "DO_SDO") (pintype "bidirectional"))
      (node (ref "D46") (pin "SDI") (pinfunction "DI_SDI") (pintype "bidirectional"))
    )
    (net (code "95") (name "Net-(D46-CO)") (class "Default")
      (node (ref "D46") (pin "CKO") (pinfunction "CO_CKO") (pintype "bidirectional"))
      (node (ref "D47") (pin "CKI") (pinfunction "CI_CKI") (pintype "bidirectional"))
    )
    (net (code "96") (name "Net-(D46-DO)") (class "Default")
      (node (ref "D46") (pin "SDO") (pinfunction "DO_SDO") (pintype "bidirectional"))
      (node (ref "D47") (pin "SDI") (pinfunction "DI_SDI") (pintype "bidirectional"))
    )
    (net (code "97") (name "Net-(D47-CO)") (class "Default")
      (node (ref "D47") (pin "CKO") (pinfunction "CO_CKO") (pintype "bidirectional"))
      (node (ref "D48") (pin "CKI") (pinfunction "CI_CKI") (pintype "bidirectional"))
    )
    (net (code "98") (name "Net-(D47-DO)") (class "Default")
      (node (ref "D47") (pin "SDO") (pinfunction "DO_SDO") (pintype "bidirectional"))
      (node (ref "D48") (pin "SDI") (pinfunction "DI_SDI") (pintype "bidirectional"))
    )
    (net (code "99") (name "Net-(D48-CO)") (class "Default")
      (node (ref "D48") (pin "CKO") (pinfunction "CO_CKO") (pintype "bidirectional"))
      (node (ref "D49") (pin "CKI") (pinfunction "CI_CKI") (pintype "bidirectional"))
    )
    (net (code "100") (name "Net-(D48-DO)") (class "Default")
      (node (ref "D48") (pin "SDO") (pinfunction "DO_SDO") (pintype "bidirectional"))
      (node (ref "D49") (pin "SDI") (pinfunction "DI_SDI") (pintype "bidirectional"))
    )
    (net (code "101") (name "Net-(D49-CO)") (class "Default")
      (node (ref "D49") (pin "CKO") (pinfunction "CO_CKO") (pintype "bidirectional"))
      (node (ref "D50") (pin "CKI") (pinfunction "CI_CKI") (pintype "bidirectional"))
    )
    (net (code "102") (name "Net-(D49-DO)") (class "Default")
      (node (ref "D49") (pin "SDO") (pinfunction "DO_SDO") (pintype "bidirectional"))
      (node (ref "D50") (pin "SDI") (pinfunction "DI_SDI") (pintype "bidirectional"))
    )
    (net (code "103") (name "Net-(D50-CO)") (class "Default")
      (node (ref "D50") (pin "CKO") (pinfunction "CO_CKO") (pintype "bidirectional"))
      (node (ref "D51") (pin "CKI") (pinfunction "CI_CKI") (pintype "bidirectional"))
    )
    (net (code "104") (name "Net-(D50-DO)") (class "Default")
      (node (ref "D50") (pin "SDO") (pinfunction "DO_SDO") (pintype "bidirectional"))
      (node (ref "D51") (pin "SDI") (pinfunction "DI_SDI") (pintype "bidirectional"))
    )
    (net (code "105") (name "Net-(D51-CO)") (class "Default")
      (node (ref "D51") (pin "CKO") (pinfunction "CO_CKO") (pintype "bidirectional"))
      (node (ref "D52") (pin "CKI") (pinfunction "CI_CKI") (pintype "bidirectional"))
    )
    (net (code "106") (name "Net-(D51-DO)") (class "Default")
      (node (ref "D51") (pin "SDO") (pinfunction "DO_SDO") (pintype "bidirectional"))
      (node (ref "D52") (pin "SDI") (pinfunction "DI_SDI") (pintype "bidirectional"))
    )
    (net (code "107") (name "Net-(D52-CO)") (class "Default")
      (node (ref "D52") (pin "CKO") (pinfunction "CO_CKO") (pintype "bidirectional"))
      (node (ref "D53") (pin "CKI") (pinfunction "CI_CKI") (pintype "bidirectional"))
    )
    (net (code "108") (name "Net-(D52-DO)") (class "Default")
      (node (ref "D52") (pin "SDO") (pinfunction "DO_SDO") (pintype "bidirectional"))
      (node (ref "D53") (pin "SDI") (pinfunction "DI_SDI") (pintype "bidirectional"))
    )
    (net (code "109") (name "Net-(D53-CO)") (class "Default")
      (node (ref "D53") (pin "CKO") (pinfunction "CO_CKO") (pintype "bidirectional"))
      (node (ref "D54") (pin "CKI") (pinfunction "CI_CKI") (pintype "bidirectional"))
    )
    (net (code "110") (name "Net-(D53-DO)") (class "Default")
      (node (ref "D53") (pin "SDO") (pinfunction "DO_SDO") (pintype "bidirectional"))
      (node (ref "D54") (pin "SDI") (pinfunction "DI_SDI") (pintype "bidirectional"))
    )
    (net (code "111") (name "Net-(D54-CO)") (class "Default")
      (node (ref "D54") (pin "CKO") (pinfunction "CO_CKO") (pintype "bidirectional"))
      (node (ref "D55") (pin "CKI") (pinfunction "CI_CKI") (pintype "bidirectional"))
    )
    (net (code "112") (name "Net-(D54-DO)") (class "Default")
      (node (ref "D54") (pin "SDO") (pinfunction "DO_SDO") (pintype "bidirectional"))
      (node (ref "D55") (pin "SDI") (pinfunction "DI_SDI") (pintype "bidirectional"))
    )
    (net (code "113") (name "Net-(D55-CO)") (class "Default")
      (node (ref "D55") (pin "CKO") (pinfunction "CO_CKO") (pintype "bidirectional"))
      (node (ref "D56") (pin "CKI") (pinfunction "CI_CKI") (pintype "bidirectional"))
    )
    (net (code "114") (name "Net-(D55-DO)") (class "Default")
      (node (ref "D55") (pin "SDO") (pinfunction "DO_SDO") (pintype "bidirectional"))
      (node (ref "D56") (pin "SDI") (pinfunction "DI_SDI") (pintype "bidirectional"))
    )
    (net (code "115") (name "Net-(D56-CO)") (class "Default")
      (node (ref "D56") (pin "CKO") (pinfunction "CO_CKO") (pintype "bidirectional"))
      (node (ref "D57") (pin "CKI") (pinfunction "CI_CKI") (pintype "bidirectional"))
    )
    (net (code "116") (name "Net-(D56-DO)") (class "Default")
      (node (ref "D56") (pin "SDO") (pinfunction "DO_SDO") (pintype "bidirectional"))
      (node (ref "D57") (pin "SDI") (pinfunction "DI_SDI") (pintype "bidirectional"))
    )
    (net (code "117") (name "Net-(D57-CO)") (class "Default")
      (node (ref "D57") (pin "CKO") (pinfunction "CO_CKO") (pintype "bidirectional"))
      (node (ref "D58") (pin "CKI") (pinfunction "CI_CKI") (pintype "bidirectional"))
    )
    (net (code "118") (name "Net-(D57-DO)") (class "Default")
      (node (ref "D57") (pin "SDO") (pinfunction "DO_SDO") (pintype "bidirectional"))
      (node (ref "D58") (pin "SDI") (pinfunction "DI_SDI") (pintype "bidirectional"))
    )
    (net (code "119") (name "Net-(D58-CO)") (class "Default")
      (node (ref "D58") (pin "CKO") (pinfunction "CO_CKO") (pintype "bidirectional"))
      (node (ref "D59") (pin "CKI") (pinfunction "CI_CKI") (pintype "bidirectional"))
    )
    (net (code "120") (name "Net-(D58-DO)") (class "Default")
      (node (ref "D58") (pin "SDO") (pinfunction "DO_SDO") (pintype "bidirectional"))
      (node (ref "D59") (pin "SDI") (pinfunction "DI_SDI") (pintype "bidirectional"))
    )
    (net (code "121") (name "Net-(D59-CO)") (class "Default")
      (node (ref "D59") (pin "CKO") (pinfunction "CO_CKO") (pintype "bidirectional"))
      (node (ref "D60") (pin "CKI") (pinfunction "CI_CKI") (pintype "bidirectional"))
    )
    (net (code "122") (name "Net-(D59-DO)") (class "Default")
      (node (ref "D59") (pin "SDO") (pinfunction "DO_SDO") (pintype "bidirectional"))
      (node (ref "D60") (pin "SDI") (pinfunction "DI_SDI") (pintype "bidirectional"))
    )
    (net (code "123") (name "Net-(D60-CO)") (class "Default")
      (node (ref "D60") (pin "CKO") (pinfunction "CO_CKO") (pintype "bidirectional"))
      (node (ref "D61") (pin "CKI") (pinfunction "CI_CKI") (pintype "bidirectional"))
    )
    (net (code "124") (name "Net-(D60-DO)") (class "Default")
      (node (ref "D60") (pin "SDO") (pinfunction "DO_SDO") (pintype "bidirectional"))
      (node (ref "D61") (pin "SDI") (pinfunction "DI_SDI") (pintype "bidirectional"))
    )
    (net (code "125") (name "Net-(D61-CO)") (class "Default")
      (node (ref "D61") (pin "CKO") (pinfunction "CO_CKO") (pintype "bidirectional"))
      (node (ref "D62") (pin "CKI") (pinfunction "CI_CKI") (pintype "bidirectional"))
    )
    (net (code "126") (name "Net-(D61-DO)") (class "Default")
      (node (ref "D61") (pin "SDO") (pinfunction "DO_SDO") (pintype "bidirectional"))
      (node (ref "D62") (pin "SDI") (pinfunction "DI_SDI") (pintype "bidirectional"))
    )
    (net (code "127") (name "Net-(D62-CO)") (class "Default")
      (node (ref "D62") (pin "CKO") (pinfunction "CO_CKO") (pintype "bidirectional"))
      (node (ref "D63") (pin "CKI") (pinfunction "CI_CKI") (pintype "bidirectional"))
    )
    (net (code "128") (name "Net-(D62-DO)") (class "Default")
      (node (ref "D62") (pin "SDO") (pinfunction "DO_SDO") (pintype "bidirectional"))
      (node (ref "D63") (pin "SDI") (pinfunction "DI_SDI") (pintype "bidirectional"))
    )
    (net (code "129") (name "Net-(D63-CO)") (class "Default")
      (node (ref "D63") (pin "CKO") (pinfunction "CO_CKO") (pintype "bidirectional"))
      (node (ref "D64") (pin "CKI") (pinfunction "CI_CKI") (pintype "bidirectional"))
    )
    (net (code "130") (name "Net-(D63-DO)") (class "Default")
      (node (ref "D63") (pin "SDO") (pinfunction "DO_SDO") (pintype "bidirectional"))
      (node (ref "D64") (pin "SDI") (pinfunction "DI_SDI") (pintype "bidirectional"))
    )
    (net (code "131") (name "Net-(D64-CO)") (class "Default")
      (node (ref "D64") (pin "CKO") (pinfunction "CO_CKO") (pintype "bidirectional"))
      (node (ref "D65") (pin "CKI") (pinfunction "CI_CKI") (pintype "bidirectional"))
    )
    (net (code "132") (name "Net-(D64-DO)") (class "Default")
      (node (ref "D64") (pin "SDO") (pinfunction "DO_SDO") (pintype "bidirectional"))
      (node (ref "D65") (pin "SDI") (pinfunction "DI_SDI") (pintype "bidirectional"))
    )
    (net (code "133") (name "Net-(D65-CO)") (class "Default")
      (node (ref "D65") (pin "CKO") (pinfunction "CO_CKO") (pintype "bidirectional"))
      (node (ref "D66") (pin "CKI") (pinfunction "CI_CKI") (pintype "bidirectional"))
    )
    (net (code "134") (name "Net-(D65-DO)") (class "Default")
      (node (ref "D65") (pin "SDO") (pinfunction "DO_SDO") (pintype "bidirectional"))
      (node (ref "D66") (pin "SDI") (pinfunction "DI_SDI") (pintype "bidirectional"))
    )
    (net (code "135") (name "Net-(D66-CO)") (class "Default")
      (node (ref "D66") (pin "CKO") (pinfunction "CO_CKO") (pintype "bidirectional"))
      (node (ref "D67") (pin "CKI") (pinfunction "CI_CKI") (pintype "bidirectional"))
    )
    (net (code "136") (name "Net-(D66-DO)") (class "Default")
      (node (ref "D66") (pin "SDO") (pinfunction "DO_SDO") (pintype "bidirectional"))
      (node (ref "D67") (pin "SDI") (pinfunction "DI_SDI") (pintype "bidirectional"))
    )
    (net (code "137") (name "Net-(D67-CO)") (class "Default")
      (node (ref "D67") (pin "CKO") (pinfunction "CO_CKO") (pintype "bidirectional"))
      (node (ref "D68") (pin "CKI") (pinfunction "CI_CKI") (pintype "bidirectional"))
    )
    (net (code "138") (name "Net-(D67-DO)") (class "Default")
      (node (ref "D67") (pin "SDO") (pinfunction "DO_SDO") (pintype "bidirectional"))
      (node (ref "D68") (pin "SDI") (pinfunction "DI_SDI") (pintype "bidirectional"))
    )
    (net (code "139") (name "Net-(D68-CO)") (class "Default")
      (node (ref "D68") (pin "CKO") (pinfunction "CO_CKO") (pintype "bidirectional"))
      (node (ref "D69") (pin "CKI") (pinfunction "CI_CKI") (pintype "bidirectional"))
    )
    (net (code "140") (name "Net-(D68-DO)") (class "Default")
      (node (ref "D68") (pin "SDO") (pinfunction "DO_SDO") (pintype "bidirectional"))
      (node (ref "D69") (pin "SDI") (pinfunction "DI_SDI") (pintype "bidirectional"))
    )
    (net (code "141") (name "Net-(D69-CO)") (class "Default")
      (node (ref "D69") (pin "CKO") (pinfunction "CO_CKO") (pintype "bidirectional"))
      (node (ref "D70") (pin "CKI") (pinfunction "CI_CKI") (pintype "bidirectional"))
    )
    (net (code "142") (name "Net-(D69-DO)") (class "Default")
      (node (ref "D69") (pin "SDO") (pinfunction "DO_SDO") (pintype "bidirectional"))
      (node (ref "D70") (pin "SDI") (pinfunction "DI_SDI") (pintype "bidirectional"))
    )
    (net (code "143") (name "Net-(D70-CO)") (class "Default")
      (node (ref "D70") (pin "CKO") (pinfunction "CO_CKO") (pintype "bidirectional"))
      (node (ref "D71") (pin "CKI") (pinfunction "CI_CKI") (pintype "bidirectional"))
    )
    (net (code "144") (name "Net-(D70-DO)") (class "Default")
      (node (ref "D70") (pin "SDO") (pinfunction "DO_SDO") (pintype "bidirectional"))
      (node (ref "D71") (pin "SDI") (pinfunction "DI_SDI") (pintype "bidirectional"))
    )
    (net (code "145") (name "Net-(D71-CO)") (class "Default")
      (node (ref "D71") (pin "CKO") (pinfunction "CO_CKO") (pintype "bidirectional"))
      (node (ref "D72") (pin "CKI") (pinfunction "CI_CKI") (pintype "bidirectional"))
    )
    (net (code "146") (name "Net-(D71-DO)") (class "Default")
      (node (ref "D71") (pin "SDO") (pinfunction "DO_SDO") (pintype "bidirectional"))
      (node (ref "D72") (pin "SDI") (pinfunction "DI_SDI") (pintype "bidirectional"))
    )
    (net (code "147") (name "Net-(D72-CO)") (class "Default")
      (node (ref "D72") (pin "CKO") (pinfunction "CO_CKO") (pintype "bidirectional"))
      (node (ref "D73") (pin "CKI") (pinfunction "CI_CKI") (pintype "bidirectional"))
    )
    (net (code "148") (name "Net-(D72-DO)") (class "Default")
      (node (ref "D72") (pin "SDO") (pinfunction "DO_SDO") (pintype "bidirectional"))
      (node (ref "D73") (pin "SDI") (pinfunction "DI_SDI") (pintype "bidirectional"))
    )
    (net (code "149") (name "Net-(D73-CO)") (class "Default")
      (node (ref "D73") (pin "CKO") (pinfunction "CO_CKO") (pintype "bidirectional"))
      (node (ref "D74") (pin "CKI") (pinfunction "CI_CKI") (pintype "bidirectional"))
    )
    (net (code "150") (name "Net-(D73-DO)") (class "Default")
      (node (ref "D73") (pin "SDO") (pinfunction "DO_SDO") (pintype "bidirectional"))
      (node (ref "D74") (pin "SDI") (pinfunction "DI_SDI") (pintype "bidirectional"))
    )
    (net (code "151") (name "Net-(D74-CO)") (class "Default")
      (node (ref "D74") (pin "CKO") (pinfunction "CO_CKO") (pintype "bidirectional"))
      (node (ref "D75") (pin "CKI") (pinfunction "CI_CKI") (pintype "bidirectional"))
    )
    (net (code "152") (name "Net-(D74-DO)") (class "Default")
      (node (ref "D74") (pin "SDO") (pinfunction "DO_SDO") (pintype "bidirectional"))
      (node (ref "D75") (pin "SDI") (pinfunction "DI_SDI") (pintype "bidirectional"))
    )
    (net (code "153") (name "Net-(D75-CO)") (class "Default")
      (node (ref "D75") (pin "CKO") (pinfunction "CO_CKO") (pintype "bidirectional"))
      (node (ref "D76") (pin "CKI") (pinfunction "CI_CKI") (pintype "bidirectional"))
    )
    (net (code "154") (name "Net-(D75-DO)") (class "Default")
      (node (ref "D75") (pin "SDO") (pinfunction "DO_SDO") (pintype "bidirectional"))
      (node (ref "D76") (pin "SDI") (pinfunction "DI_SDI") (pintype "bidirectional"))
    )
    (net (code "155") (name "Net-(D76-CO)") (class "Default")
      (node (ref "D76") (pin "CKO") (pinfunction "CO_CKO") (pintype "bidirectional"))
      (node (ref "D77") (pin "CKI") (pinfunction "CI_CKI") (pintype "bidirectional"))
    )
    (net (code "156") (name "Net-(D76-DO)") (class "Default")
      (node (ref "D76") (pin "SDO") (pinfunction "DO_SDO") (pintype "bidirectional"))
      (node (ref "D77") (pin "SDI") (pinfunction "DI_SDI") (pintype "bidirectional"))
    )
    (net (code "157") (name "Net-(D77-CO)") (class "Default")
      (node (ref "D77") (pin "CKO") (pinfunction "CO_CKO") (pintype "bidirectional"))
      (node (ref "D78") (pin "CKI") (pinfunction "CI_CKI") (pintype "bidirectional"))
    )
    (net (code "158") (name "Net-(D77-DO)") (class "Default")
      (node (ref "D77") (pin "SDO") (pinfunction "DO_SDO") (pintype "bidirectional"))
      (node (ref "D78") (pin "SDI") (pinfunction "DI_SDI") (pintype "bidirectional"))
    )
    (net (code "159") (name "Net-(D78-CO)") (class "Default")
      (node (ref "D78") (pin "CKO") (pinfunction "CO_CKO") (pintype "bidirectional"))
      (node (ref "D79") (pin "CKI") (pinfunction "CI_CKI") (pintype "bidirectional"))
    )
    (net (code "160") (name "Net-(D78-DO)") (class "Default")
      (node (ref "D78") (pin "SDO") (pinfunction "DO_SDO") (pintype "bidirectional"))
      (node (ref "D79") (pin "SDI") (pinfunction "DI_SDI") (pintype "bidirectional"))
    )
    (net (code "161") (name "Net-(D79-CO)") (class "Default")
      (node (ref "D79") (pin "CKO") (pinfunction "CO_CKO") (pintype "bidirectional"))
      (node (ref "D80") (pin "CKI") (pinfunction "CI_CKI") (pintype "bidirectional"))
    )
    (net (code "162") (name "Net-(D79-DO)") (class "Default")
      (node (ref "D79") (pin "SDO") (pinfunction "DO_SDO") (pintype "bidirectional"))
      (node (ref "D80") (pin "SDI") (pinfunction "DI_SDI") (pintype "bidirectional"))
    )
    (net (code "163") (name "Net-(D80-CO)") (class "Default")
      (node (ref "D80") (pin "CKO") (pinfunction "CO_CKO") (pintype "bidirectional"))
      (node (ref "D81") (pin "CKI") (pinfunction "CI_CKI") (pintype "bidirectional"))
    )
    (net (code "164") (name "Net-(D80-DO)") (class "Default")
      (node (ref "D80") (pin "SDO") (pinfunction "DO_SDO") (pintype "bidirectional"))
      (node (ref "D81") (pin "SDI") (pinfunction "DI_SDI") (pintype "bidirectional"))
    )
    (net (code "165") (name "Net-(D81-CO)") (class "Default")
      (node (ref "D81") (pin "CKO") (pinfunction "CO_CKO") (pintype "bidirectional"))
      (node (ref "D82") (pin "CKI") (pinfunction "CI_CKI") (pintype "bidirectional"))
    )
    (net (code "166") (name "Net-(D81-DO)") (class "Default")
      (node (ref "D81") (pin "SDO") (pinfunction "DO_SDO") (pintype "bidirectional"))
      (node (ref "D82") (pin "SDI") (pinfunction "DI_SDI") (pintype "bidirectional"))
    )
    (net (code "167") (name "Net-(D82-CO)") (class "Default")
      (node (ref "D82") (pin "CKO") (pinfunction "CO_CKO") (pintype "bidirectional"))
      (node (ref "D83") (pin "CKI") (pinfunction "CI_CKI") (pintype "bidirectional"))
    )
    (net (code "168") (name "Net-(D82-DO)") (class "Default")
      (node (ref "D82") (pin "SDO") (pinfunction "DO_SDO") (pintype "bidirectional"))
      (node (ref "D83") (pin "SDI") (pinfunction "DI_SDI") (pintype "bidirectional"))
    )
    (net (code "169") (name "Net-(D83-CO)") (class "Default")
      (node (ref "D83") (pin "CKO") (pinfunction "CO_CKO") (pintype "bidirectional"))
      (node (ref "D84") (pin "CKI") (pinfunction "CI_CKI") (pintype "bidirectional"))
    )
    (net (code "170") (name "Net-(D83-DO)") (class "Default")
      (node (ref "D83") (pin "SDO") (pinfunction "DO_SDO") (pintype "bidirectional"))
      (node (ref "D84") (pin "SDI") (pinfunction "DI_SDI") (pintype "bidirectional"))
    )
    (net (code "171") (name "Net-(D84-CO)") (class "Default")
      (node (ref "D84") (pin "CKO") (pinfunction "CO_CKO") (pintype "bidirectional"))
      (node (ref "D85") (pin "CKI") (pinfunction "CI_CKI") (pintype "bidirectional"))
    )
    (net (code "172") (name "Net-(D84-DO)") (class "Default")
      (node (ref "D84") (pin "SDO") (pinfunction "DO_SDO") (pintype "bidirectional"))
      (node (ref "D85") (pin "SDI") (pinfunction "DI_SDI") (pintype "bidirectional"))
    )
    (net (code "173") (name "Net-(D85-CO)") (class "Default")
      (node (ref "D85") (pin "CKO") (pinfunction "CO_CKO") (pintype "bidirectional"))
      (node (ref "D86") (pin "CKI") (pinfunction "CI_CKI") (pintype "bidirectional"))
    )
    (net (code "174") (name "Net-(D85-DO)") (class "Default")
      (node (ref "D85") (pin "SDO") (pinfunction "DO_SDO") (pintype "bidirectional"))
      (node (ref "D86") (pin "SDI") (pinfunction "DI_SDI") (pintype "bidirectional"))
    )
    (net (code "175") (name "Net-(D86-CO)") (class "Default")
      (node (ref "D86") (pin "CKO") (pinfunction "CO_CKO") (pintype "bidirectional"))
      (node (ref "D87") (pin "CKI") (pinfunction "CI_CKI") (pintype "bidirectional"))
    )
    (net (code "176") (name "Net-(D86-DO)") (class "Default")
      (node (ref "D86") (pin "SDO") (pinfunction "DO_SDO") (pintype "bidirectional"))
      (node (ref "D87") (pin "SDI") (pinfunction "DI_SDI") (pintype "bidirectional"))
    )
    (net (code "177") (name "Net-(D87-CO)") (class "Default")
      (node (ref "D87") (pin "CKO") (pinfunction "CO_CKO") (pintype "bidirectional"))
      (node (ref "D88") (pin "CKI") (pinfunction "CI_CKI") (pintype "bidirectional"))
    )
    (net (code "178") (name "Net-(D87-DO)") (class "Default")
      (node (ref "D87") (pin "SDO") (pinfunction "DO_SDO") (pintype "bidirectional"))
      (node (ref "D88") (pin "SDI") (pinfunction "DI_SDI") (pintype "bidirectional"))
    )
    (net (code "179") (name "Net-(D88-CO)") (class "Default")
      (node (ref "D88") (pin "CKO") (pinfunction "CO_CKO") (pintype "bidirectional"))
      (node (ref "D89") (pin "CKI") (pinfunction "CI_CKI") (pintype "bidirectional"))
    )
    (net (code "180") (name "Net-(D88-DO)") (class "Default")
      (node (ref "D88") (pin "SDO") (pinfunction "DO_SDO") (pintype "bidirectional"))
      (node (ref "D89") (pin "SDI") (pinfunction "DI_SDI") (pintype "bidirectional"))
    )
    (net (code "181") (name "Net-(D89-CO)") (class "Default")
      (node (ref "D89") (pin "CKO") (pinfunction "CO_CKO") (pintype "bidirectional"))
      (node (ref "D90") (pin "CKI") (pinfunction "CI_CKI") (pintype "bidirectional"))
    )
    (net (code "182") (name "Net-(D89-DO)") (class "Default")
      (node (ref "D89") (pin "SDO") (pinfunction "DO_SDO") (pintype "bidirectional"))
      (node (ref "D90") (pin "SDI") (pinfunction "DI_SDI") (pintype "bidirectional"))
    )
    (net (code "183") (name "Net-(D90-CO)") (class "Default")
      (node (ref "D90") (pin "CKO") (pinfunction "CO_CKO") (pintype "bidirectional"))
      (node (ref "D91") (pin "CKI") (pinfunction "CI_CKI") (pintype "bidirectional"))
    )
    (net (code "184") (name "Net-(D90-DO)") (class "Default")
      (node (ref "D90") (pin "SDO") (pinfunction "DO_SDO") (pintype "bidirectional"))
      (node (ref "D91") (pin "SDI") (pinfunction "DI_SDI") (pintype "bidirectional"))
    )
    (net (code "185") (name "Net-(D91-CO)") (class "Default")
      (node (ref "D91") (pin "CKO") (pinfunction "CO_CKO") (pintype "bidirectional"))
      (node (ref "D92") (pin "CKI") (pinfunction "CI_CKI") (pintype "bidirectional"))
    )
    (net (code "186") (name "Net-(D91-DO)") (class "Default")
      (node (ref "D91") (pin "SDO") (pinfunction "DO_SDO") (pintype "bidirectional"))
      (node (ref "D92") (pin "SDI") (pinfunction "DI_SDI") (pintype "bidirectional"))
    )
    (net (code "187") (name "Net-(D92-CO)") (class "Default")
      (node (ref "D92") (pin "CKO") (pinfunction "CO_CKO") (pintype "bidirectional"))
      (node (ref "D93") (pin "CKI") (pinfunction "CI_CKI") (pintype "bidirectional"))
    )
    (net (code "188") (name "Net-(D92-DO)") (class "Default")
      (node (ref "D92") (pin "SDO") (pinfunction "DO_SDO") (pintype "bidirectional"))
      (node (ref "D93") (pin "SDI") (pinfunction "DI_SDI") (pintype "bidirectional"))
    )
    (net (code "189") (name "Net-(D93-CO)") (class "Default")
      (node (ref "D93") (pin "CKO") (pinfunction "CO_CKO") (pintype "bidirectional"))
      (node (ref "D94") (pin "CKI") (pinfunction "CI_CKI") (pintype "bidirectional"))
    )
    (net (code "190") (name "Net-(D93-DO)") (class "Default")
      (node (ref "D93") (pin "SDO") (pinfunction "DO_SDO") (pintype "bidirectional"))
      (node (ref "D94") (pin "SDI") (pinfunction "DI_SDI") (pintype "bidirectional"))
    )
    (net (code "191") (name "Net-(D94-CO)") (class "Default")
      (node (ref "D94") (pin "CKO") (pinfunction "CO_CKO") (pintype "bidirectional"))
      (node (ref "D95") (pin "CKI") (pinfunction "CI_CKI") (pintype "bidirectional"))
    )
    (net (code "192") (name "Net-(D94-DO)") (class "Default")
      (node (ref "D94") (pin "SDO") (pinfunction "DO_SDO") (pintype "bidirectional"))
      (node (ref "D95") (pin "SDI") (pinfunction "DI_SDI") (pintype "bidirectional"))
    )
    (net (code "193") (name "Net-(D95-CO)") (class "Default")
      (node (ref "D95") (pin "CKO") (pinfunction "CO_CKO") (pintype "bidirectional"))
      (node (ref "D96") (pin "CKI") (pinfunction "CI_CKI") (pintype "bidirectional"))
    )
    (net (code "194") (name "Net-(D95-DO)") (class "Default")
      (node (ref "D95") (pin "SDO") (pinfunction "DO_SDO") (pintype "bidirectional"))
      (node (ref "D96") (pin "SDI") (pinfunction "DI_SDI") (pintype "bidirectional"))
    )
    (net (code "195") (name "Net-(D96-CO)") (class "Default")
      (node (ref "D96") (pin "CKO") (pinfunction "CO_CKO") (pintype "bidirectional"))
      (node (ref "D97") (pin "CKI") (pinfunction "CI_CKI") (pintype "bidirectional"))
    )
    (net (code "196") (name "Net-(D96-DO)") (class "Default")
      (node (ref "D96") (pin "SDO") (pinfunction "DO_SDO") (pintype "bidirectional"))
      (node (ref "D97") (pin "SDI") (pinfunction "DI_SDI") (pintype "bidirectional"))
    )
    (net (code "197") (name "Net-(D97-CO)") (class "Default")
      (node (ref "D97") (pin "CKO") (pinfunction "CO_CKO") (pintype "bidirectional"))
      (node (ref "D98") (pin "CKI") (pinfunction "CI_CKI") (pintype "bidirectional"))
    )
    (net (code "198") (name "Net-(D97-DO)") (class "Default")
      (node (ref "D97") (pin "SDO") (pinfunction "DO_SDO") (pintype "bidirectional"))
      (node (ref "D98") (pin "SDI") (pinfunction "DI_SDI") (pintype "bidirectional"))
    )
    (net (code "199") (name "Net-(D98-CO)") (class "Default")
      (node (ref "D98") (pin "CKO") (pinfunction "CO_CKO") (pintype "bidirectional"))
      (node (ref "D99") (pin "CKI") (pinfunction "CI_CKI") (pintype "bidirectional"))
    )
    (net (code "200") (name "Net-(D98-DO)") (class "Default")
      (node (ref "D98") (pin "SDO") (pinfunction "DO_SDO") (pintype "bidirectional"))
      (node (ref "D99") (pin "SDI") (pinfunction "DI_SDI") (pintype "bidirectional"))
    )
    (net (code "201") (name "Net-(D100-CI)") (class "Default")
      (node (ref "D100") (pin "CKI") (pinfunction "CI_CKI") (pintype "bidirectional"))
      (node (ref "D99") (pin "CKO") (pinfunction "CO_CKO") (pintype "bidirectional"))
    )
    (net (code "202") (name "Net-(D100-CO)") (class "Default")
      (node (ref "D100") (pin "CKO") (pinfunction "CO_CKO") (pintype "bidirectional"))
      (node (ref "J3") (pin "P$2") (pinfunction "2_P$2") (pintype "passive"))
    )
    (net (code "203") (name "Net-(D100-DI)") (class "Default")
      (node (ref "D100") (pin "SDI") (pinfunction "DI_SDI") (pintype "bidirectional"))
      (node (ref "D99") (pin "SDO") (pinfunction "DO_SDO") (pintype "bidirectional"))
    )
    (net (code "204") (name "Net-(D100-DO)") (class "Default")
      (node (ref "D100") (pin "SDO") (pinfunction "DO_SDO") (pintype "bidirectional"))
      (node (ref "J3") (pin "P$1") (pinfunction "1_P$1") (pintype "passive"))
    )
  )
)
